# 5409668.net
KiCad netlist of a schematic drawn in EAGLE
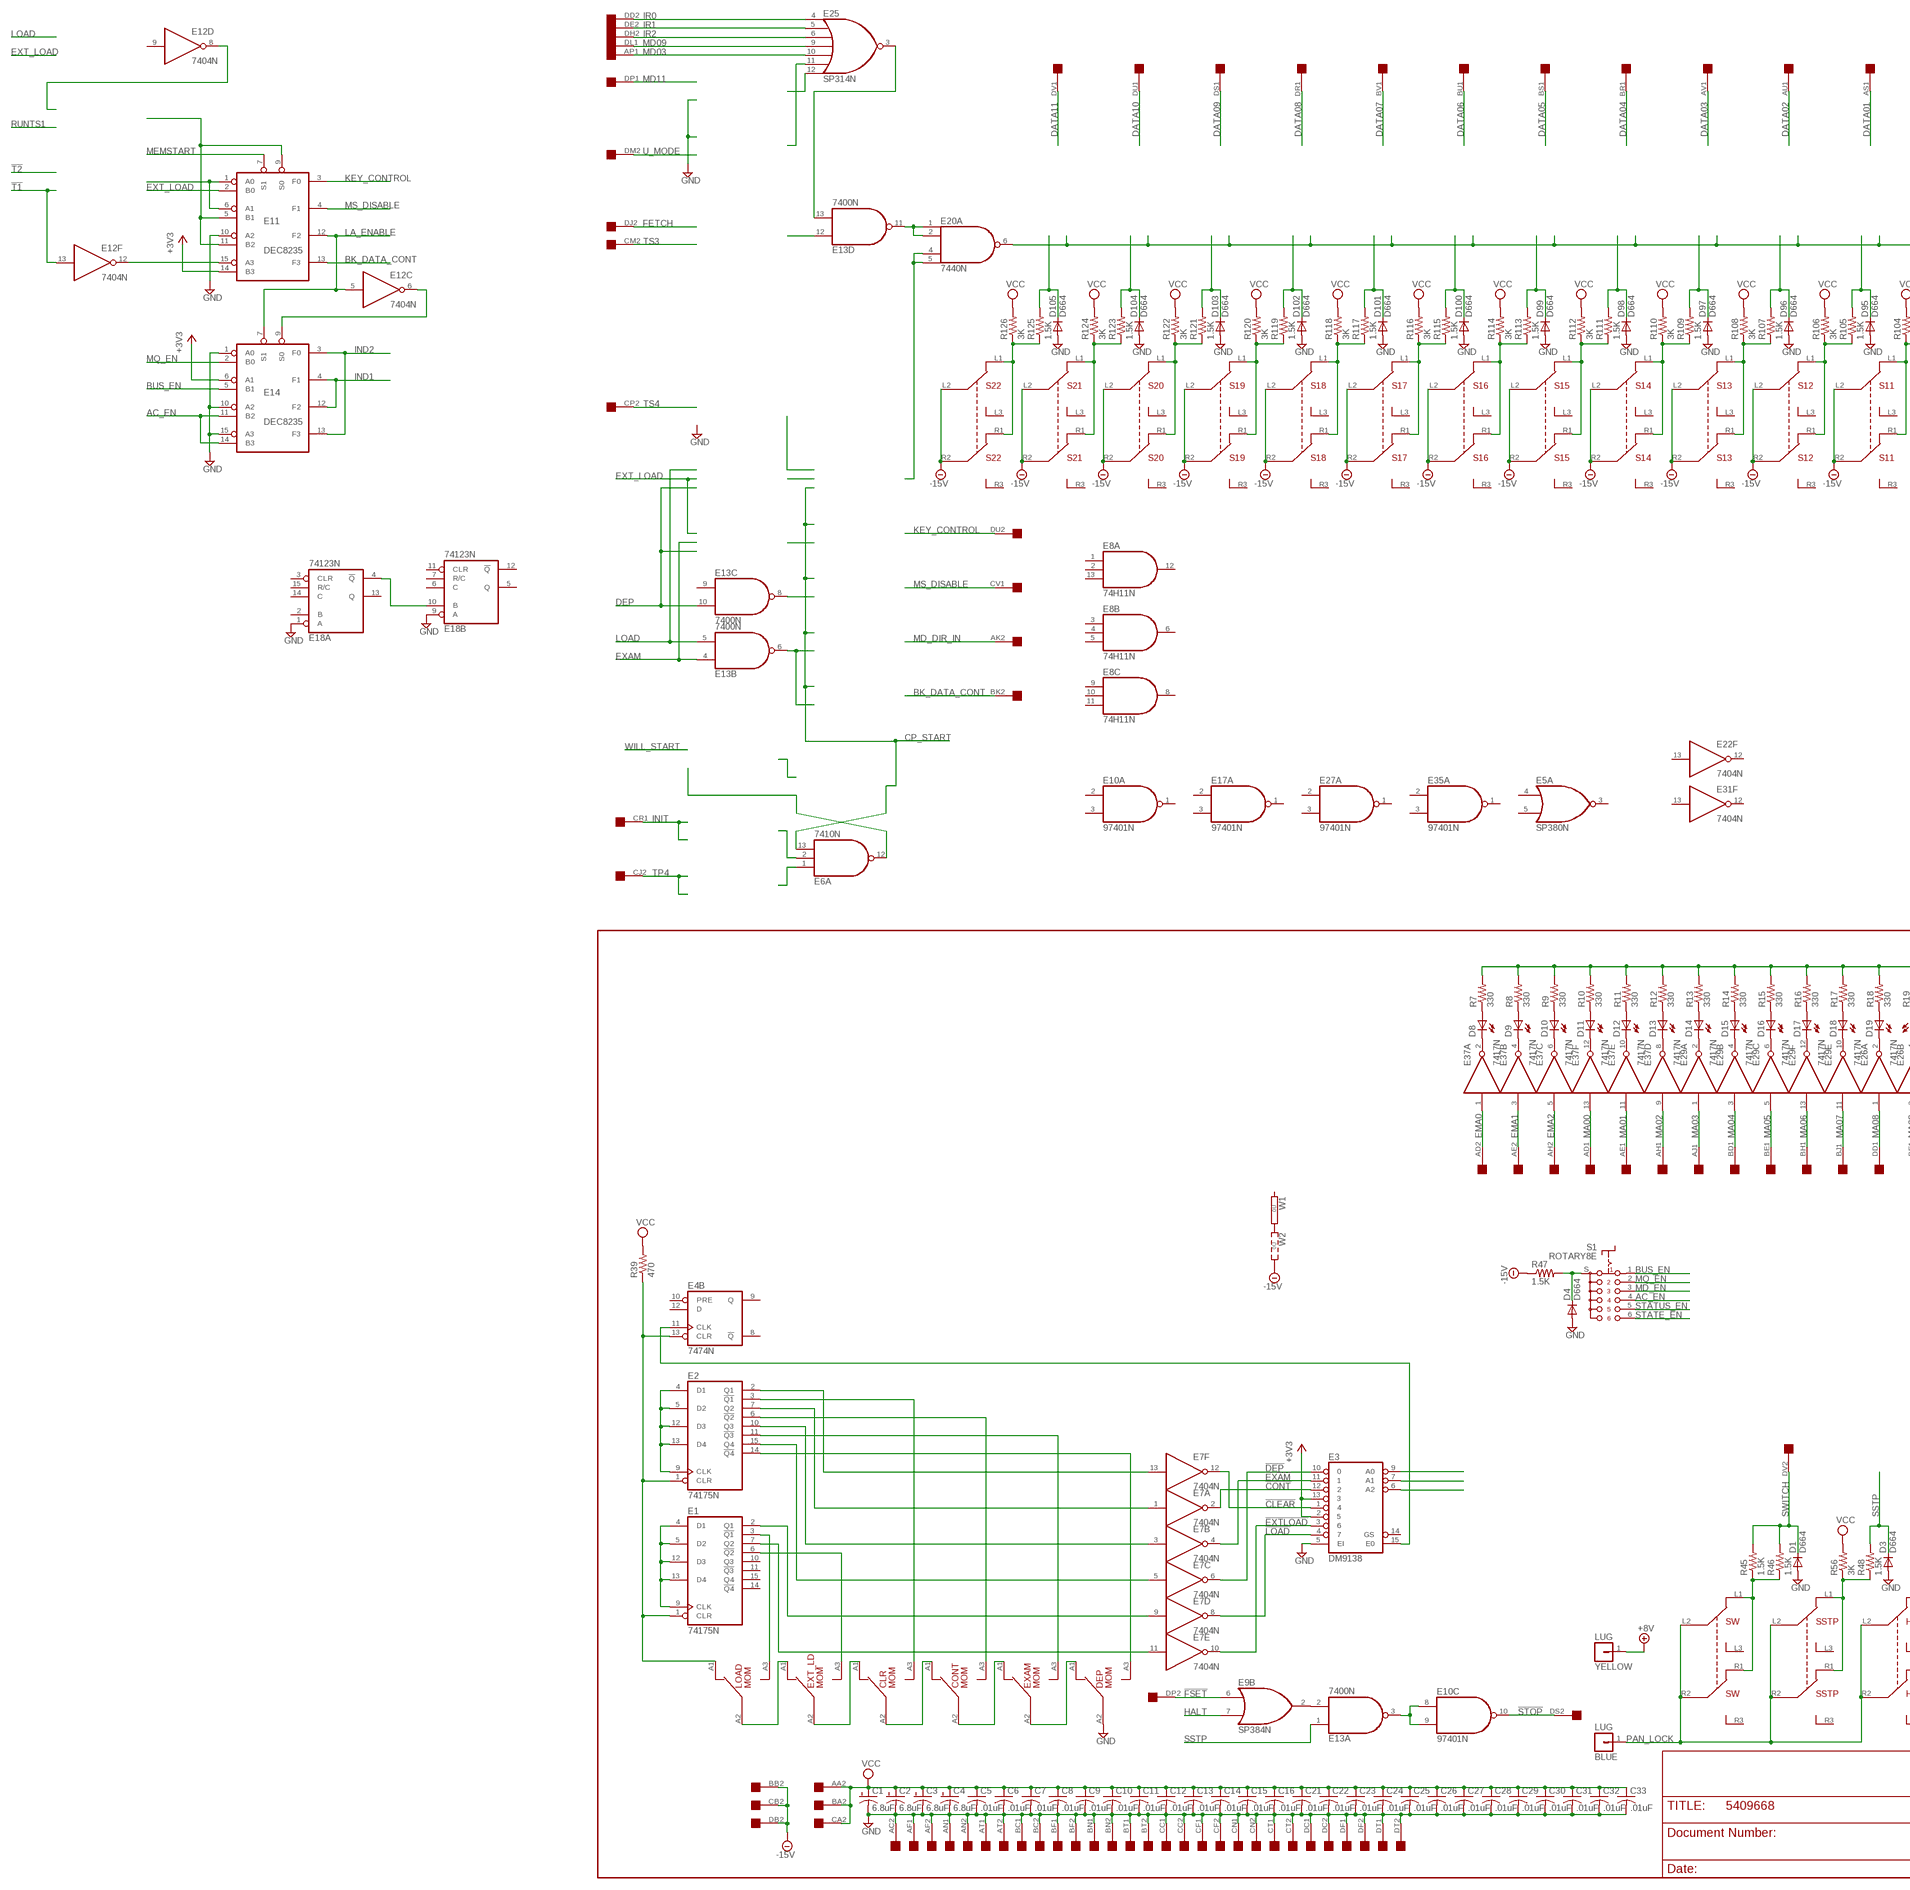
[diagram p0: schematic, sheet 1, part 1 of 2]
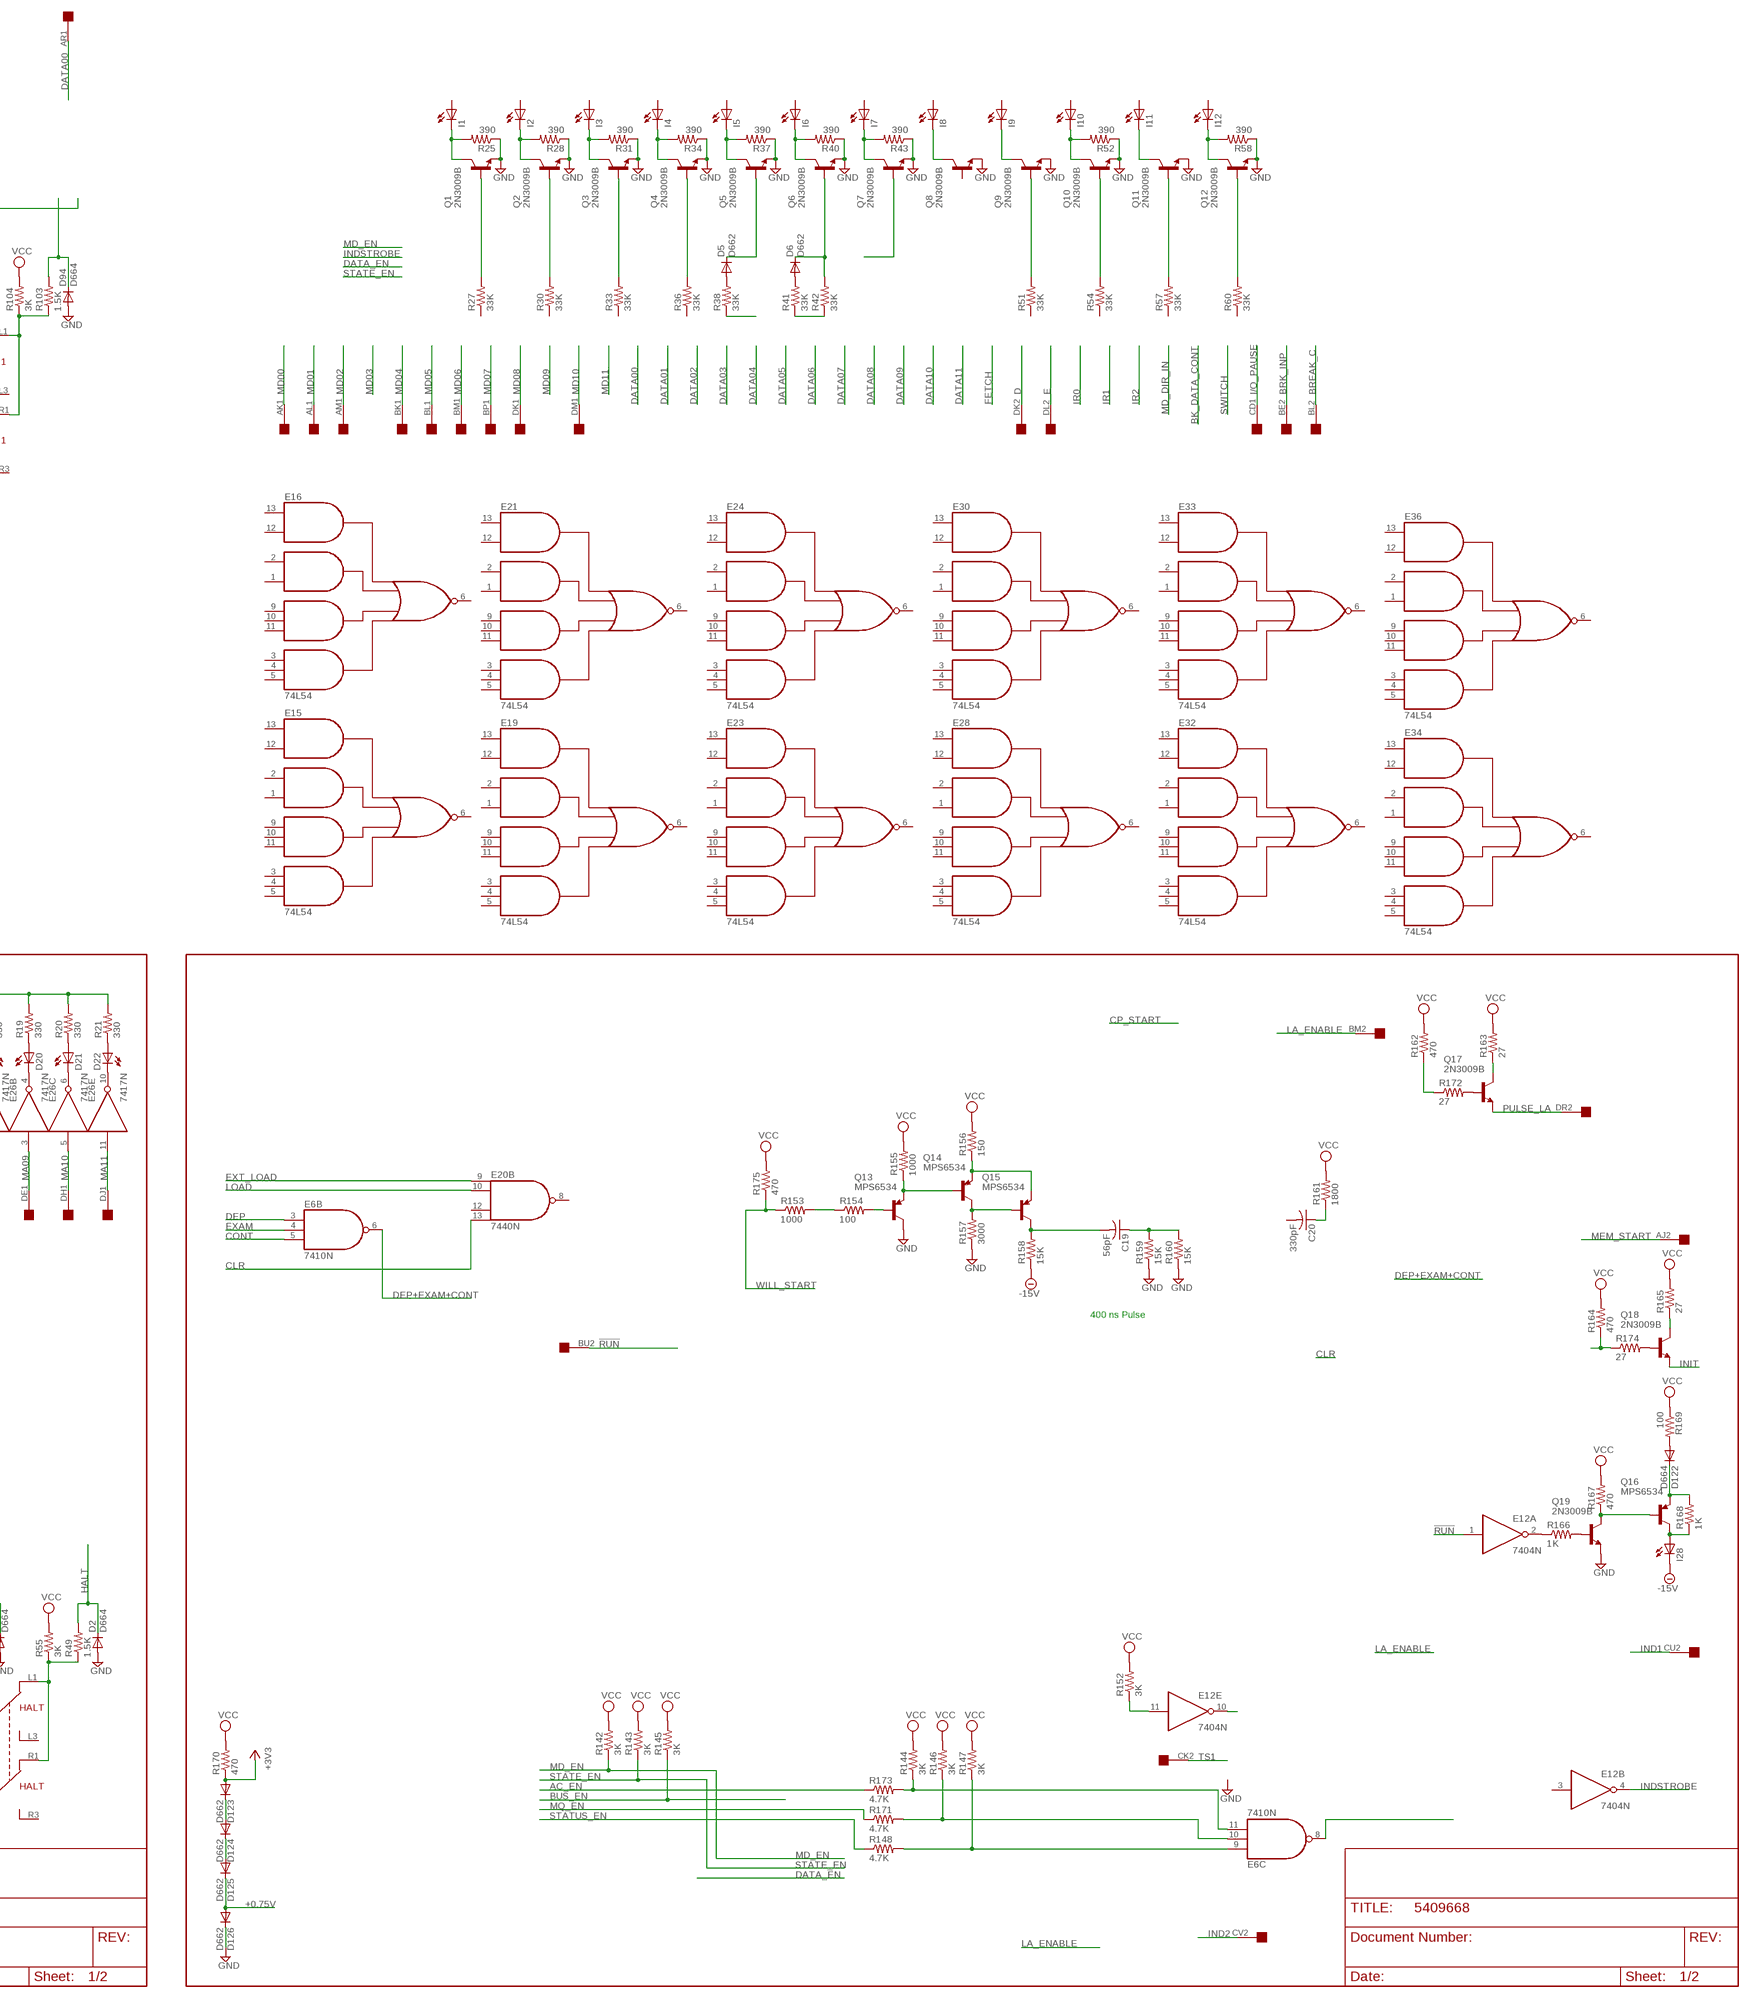
[diagram p1: schematic, sheet 1, part 2 of 2]

(export (version "E")
  (design (tool "Eeschema 10.0.6"))
  (components
    (comp (ref "BLUE")
      (value "LUG")
      (footprint "eagle-import:SPADELUG")
      (libsource (lib "eagle-import") (part "LUG"))
    )
    (comp (ref "C1")
      (value "6.8uF")
      (footprint "eagle-import:E12-8")
      (libsource (lib "eagle-import") (part "CPOL-USE20-8AXIAL"))
    )
    (comp (ref "C2")
      (value "6.8uF")
      (footprint "eagle-import:E12-8")
      (libsource (lib "eagle-import") (part "CPOL-USE20-8AXIAL"))
    )
    (comp (ref "C3")
      (value "6.8uF")
      (footprint "eagle-import:E12-8")
      (libsource (lib "eagle-import") (part "CPOL-USE20-8AXIAL"))
    )
    (comp (ref "C4")
      (value "6.8uF")
      (footprint "eagle-import:E12-8")
      (libsource (lib "eagle-import") (part "CPOL-USE20-8AXIAL"))
    )
    (comp (ref "C5")
      (value ".01uF")
      (footprint "eagle-import:C050-025X075")
      (libsource (lib "eagle-import") (part "C-US050-025X075"))
    )
    (comp (ref "C6")
      (value ".01uF")
      (footprint "eagle-import:C050-025X075")
      (libsource (lib "eagle-import") (part "C-US050-025X075"))
    )
    (comp (ref "C7")
      (value ".01uF")
      (footprint "eagle-import:C050-025X075")
      (libsource (lib "eagle-import") (part "C-US050-025X075"))
    )
    (comp (ref "C8")
      (value ".01uF")
      (footprint "eagle-import:C050-025X075")
      (libsource (lib "eagle-import") (part "C-US050-025X075"))
    )
    (comp (ref "C9")
      (value ".01uF")
      (footprint "eagle-import:C050-025X075")
      (libsource (lib "eagle-import") (part "C-US050-025X075"))
    )
    (comp (ref "C10")
      (value ".01uF")
      (footprint "eagle-import:C050-025X075")
      (libsource (lib "eagle-import") (part "C-US050-025X075"))
    )
    (comp (ref "C11")
      (value ".01uF")
      (footprint "eagle-import:C050-025X075")
      (libsource (lib "eagle-import") (part "C-US050-025X075"))
    )
    (comp (ref "C12")
      (value ".01uF")
      (footprint "eagle-import:C050-025X075")
      (libsource (lib "eagle-import") (part "C-US050-025X075"))
    )
    (comp (ref "C13")
      (value ".01uF")
      (footprint "eagle-import:C050-025X075")
      (libsource (lib "eagle-import") (part "C-US050-025X075"))
    )
    (comp (ref "C14")
      (value ".01uF")
      (footprint "eagle-import:C050-025X075")
      (libsource (lib "eagle-import") (part "C-US050-025X075"))
    )
    (comp (ref "C15")
      (value ".01uF")
      (footprint "eagle-import:C050-025X075")
      (libsource (lib "eagle-import") (part "C-US050-025X075"))
    )
    (comp (ref "C16")
      (value ".01uF")
      (footprint "eagle-import:C050-025X075")
      (libsource (lib "eagle-import") (part "C-US050-025X075"))
    )
    (comp (ref "C19")
      (value "56pF")
      (footprint "eagle-import:C050-025X075")
      (libsource (lib "eagle-import") (part "C-US050-025X075"))
    )
    (comp (ref "C20")
      (value "330pF")
      (footprint "eagle-import:C050-025X075")
      (libsource (lib "eagle-import") (part "C-US050-025X075"))
    )
    (comp (ref "C21")
      (value ".01uF")
      (footprint "eagle-import:C050-025X075")
      (libsource (lib "eagle-import") (part "C-US050-025X075"))
    )
    (comp (ref "C22")
      (value ".01uF")
      (footprint "eagle-import:C050-025X075")
      (libsource (lib "eagle-import") (part "C-US050-025X075"))
    )
    (comp (ref "C23")
      (value ".01uF")
      (footprint "eagle-import:C050-025X075")
      (libsource (lib "eagle-import") (part "C-US050-025X075"))
    )
    (comp (ref "C24")
      (value ".01uF")
      (footprint "eagle-import:C050-025X075")
      (libsource (lib "eagle-import") (part "C-US050-025X075"))
    )
    (comp (ref "C25")
      (value ".01uF")
      (footprint "eagle-import:C050-025X075")
      (libsource (lib "eagle-import") (part "C-US050-025X075"))
    )
    (comp (ref "C26")
      (value ".01uF")
      (footprint "eagle-import:C050-025X075")
      (libsource (lib "eagle-import") (part "C-US050-025X075"))
    )
    (comp (ref "C27")
      (value ".01uF")
      (footprint "eagle-import:C050-025X075")
      (libsource (lib "eagle-import") (part "C-US050-025X075"))
    )
    (comp (ref "C28")
      (value ".01uF")
      (footprint "eagle-import:C050-025X075")
      (libsource (lib "eagle-import") (part "C-US050-025X075"))
    )
    (comp (ref "C29")
      (value ".01uF")
      (footprint "eagle-import:C050-025X075")
      (libsource (lib "eagle-import") (part "C-US050-025X075"))
    )
    (comp (ref "C30")
      (value ".01uF")
      (footprint "eagle-import:C050-025X075")
      (libsource (lib "eagle-import") (part "C-US050-025X075"))
    )
    (comp (ref "C31")
      (value ".01uF")
      (footprint "eagle-import:C050-025X075")
      (libsource (lib "eagle-import") (part "C-US050-025X075"))
    )
    (comp (ref "C32")
      (value ".01uF")
      (footprint "eagle-import:C050-025X075")
      (libsource (lib "eagle-import") (part "C-US050-025X075"))
    )
    (comp (ref "C33")
      (value ".01uF")
      (footprint "eagle-import:C050-025X075")
      (libsource (lib "eagle-import") (part "C-US050-025X075"))
    )
    (comp (ref "CLR")
      (value "SPDT8I")
      (footprint "eagle-import:SPDT8I")
      (libsource (lib "eagle-import") (part "SPDT8I"))
    )
    (comp (ref "CONT")
      (value "SPDT8I")
      (footprint "eagle-import:SPDT8I")
      (libsource (lib "eagle-import") (part "SPDT8I"))
    )
    (comp (ref "D1")
      (value "D664")
      (footprint "eagle-import:DO35-10")
      (libsource (lib "eagle-import") (part "1N4148DO35-10"))
    )
    (comp (ref "D2")
      (value "D664")
      (footprint "eagle-import:DO35-10")
      (libsource (lib "eagle-import") (part "1N4148DO35-10"))
    )
    (comp (ref "D3")
      (value "D664")
      (footprint "eagle-import:DO35-10")
      (libsource (lib "eagle-import") (part "1N4148DO35-10"))
    )
    (comp (ref "D4")
      (value "D664")
      (footprint "eagle-import:DO35-10")
      (libsource (lib "eagle-import") (part "1N4148DO35-10"))
    )
    (comp (ref "D5")
      (value "D662")
      (footprint "eagle-import:DO35-10")
      (libsource (lib "eagle-import") (part "1N4148DO35-10"))
    )
    (comp (ref "D6")
      (value "D662")
      (footprint "eagle-import:DO35-10")
      (libsource (lib "eagle-import") (part "1N4148DO35-10"))
    )
    (comp (ref "D8")
      (value "LED5MM")
      (footprint "eagle-import:LED5MM")
      (libsource (lib "eagle-import") (part "LED5MM"))
    )
    (comp (ref "D9")
      (value "LED5MM")
      (footprint "eagle-import:LED5MM")
      (libsource (lib "eagle-import") (part "LED5MM"))
    )
    (comp (ref "D10")
      (value "LED5MM")
      (footprint "eagle-import:LED5MM")
      (libsource (lib "eagle-import") (part "LED5MM"))
    )
    (comp (ref "D11")
      (value "LED5MM")
      (footprint "eagle-import:LED5MM")
      (libsource (lib "eagle-import") (part "LED5MM"))
    )
    (comp (ref "D12")
      (value "LED5MM")
      (footprint "eagle-import:LED5MM")
      (libsource (lib "eagle-import") (part "LED5MM"))
    )
    (comp (ref "D13")
      (value "LED5MM")
      (footprint "eagle-import:LED5MM")
      (libsource (lib "eagle-import") (part "LED5MM"))
    )
    (comp (ref "D14")
      (value "LED5MM")
      (footprint "eagle-import:LED5MM")
      (libsource (lib "eagle-import") (part "LED5MM"))
    )
    (comp (ref "D15")
      (value "LED5MM")
      (footprint "eagle-import:LED5MM")
      (libsource (lib "eagle-import") (part "LED5MM"))
    )
    (comp (ref "D16")
      (value "LED5MM")
      (footprint "eagle-import:LED5MM")
      (libsource (lib "eagle-import") (part "LED5MM"))
    )
    (comp (ref "D17")
      (value "LED5MM")
      (footprint "eagle-import:LED5MM")
      (libsource (lib "eagle-import") (part "LED5MM"))
    )
    (comp (ref "D18")
      (value "LED5MM")
      (footprint "eagle-import:LED5MM")
      (libsource (lib "eagle-import") (part "LED5MM"))
    )
    (comp (ref "D19")
      (value "LED5MM")
      (footprint "eagle-import:LED5MM")
      (libsource (lib "eagle-import") (part "LED5MM"))
    )
    (comp (ref "D20")
      (value "LED5MM")
      (footprint "eagle-import:LED5MM")
      (libsource (lib "eagle-import") (part "LED5MM"))
    )
    (comp (ref "D21")
      (value "LED5MM")
      (footprint "eagle-import:LED5MM")
      (libsource (lib "eagle-import") (part "LED5MM"))
    )
    (comp (ref "D22")
      (value "LED5MM")
      (footprint "eagle-import:LED5MM")
      (libsource (lib "eagle-import") (part "LED5MM"))
    )
    (comp (ref "D94")
      (value "D664")
      (footprint "eagle-import:DO35-10")
      (libsource (lib "eagle-import") (part "1N4148DO35-10"))
    )
    (comp (ref "D95")
      (value "D664")
      (footprint "eagle-import:DO35-10")
      (libsource (lib "eagle-import") (part "1N4148DO35-10"))
    )
    (comp (ref "D96")
      (value "D664")
      (footprint "eagle-import:DO35-10")
      (libsource (lib "eagle-import") (part "1N4148DO35-10"))
    )
    (comp (ref "D97")
      (value "D664")
      (footprint "eagle-import:DO35-10")
      (libsource (lib "eagle-import") (part "1N4148DO35-10"))
    )
    (comp (ref "D98")
      (value "D664")
      (footprint "eagle-import:DO35-10")
      (libsource (lib "eagle-import") (part "1N4148DO35-10"))
    )
    (comp (ref "D99")
      (value "D664")
      (footprint "eagle-import:DO35-10")
      (libsource (lib "eagle-import") (part "1N4148DO35-10"))
    )
    (comp (ref "D100")
      (value "D664")
      (footprint "eagle-import:DO35-10")
      (libsource (lib "eagle-import") (part "1N4148DO35-10"))
    )
    (comp (ref "D101")
      (value "D664")
      (footprint "eagle-import:DO35-10")
      (libsource (lib "eagle-import") (part "1N4148DO35-10"))
    )
    (comp (ref "D102")
      (value "D664")
      (footprint "eagle-import:DO35-10")
      (libsource (lib "eagle-import") (part "1N4148DO35-10"))
    )
    (comp (ref "D103")
      (value "D664")
      (footprint "eagle-import:DO35-10")
      (libsource (lib "eagle-import") (part "1N4148DO35-10"))
    )
    (comp (ref "D104")
      (value "D664")
      (footprint "eagle-import:DO35-10")
      (libsource (lib "eagle-import") (part "1N4148DO35-10"))
    )
    (comp (ref "D105")
      (value "D664")
      (footprint "eagle-import:DO35-10")
      (libsource (lib "eagle-import") (part "1N4148DO35-10"))
    )
    (comp (ref "D122")
      (value "D664")
      (footprint "eagle-import:DO35-10")
      (libsource (lib "eagle-import") (part "1N4148DO35-10"))
    )
    (comp (ref "D123")
      (value "D662")
      (footprint "eagle-import:DO35-10")
      (libsource (lib "eagle-import") (part "1N4148DO35-10"))
    )
    (comp (ref "D124")
      (value "D662")
      (footprint "eagle-import:DO35-10")
      (libsource (lib "eagle-import") (part "1N4148DO35-10"))
    )
    (comp (ref "D125")
      (value "D662")
      (footprint "eagle-import:DO35-10")
      (libsource (lib "eagle-import") (part "1N4148DO35-10"))
    )
    (comp (ref "D126")
      (value "D662")
      (footprint "eagle-import:DO35-10")
      (libsource (lib "eagle-import") (part "1N4148DO35-10"))
    )
    (comp (ref "DEP")
      (value "SPDT8I")
      (footprint "eagle-import:SPDT8I")
      (libsource (lib "eagle-import") (part "SPDT8I"))
    )
    (comp (ref "E1")
      (value "74175N")
      (footprint "eagle-import:DIL16")
      (libsource (lib "eagle-import") (part "74175N"))
    )
    (comp (ref "E2")
      (value "74175N")
      (footprint "eagle-import:DIL16")
      (libsource (lib "eagle-import") (part "74175N"))
    )
    (comp (ref "E3")
      (value "DM9138")
      (footprint "eagle-import:DIL16")
      (libsource (lib "eagle-import") (part "74348NLS"))
    )
    (comp (ref "E4")
      (value "7474N")
      (footprint "eagle-import:DIL14")
      (libsource (lib "eagle-import") (part "7474NS"))
    )
    (comp (ref "E5")
      (value "SP380N")
      (footprint "eagle-import:DIL14")
      (libsource (lib "eagle-import") (part "SP380N"))
    )
    (comp (ref "E6")
      (value "7410N")
      (footprint "eagle-import:DIL14")
      (libsource (lib "eagle-import") (part "7410N"))
    )
    (comp (ref "E7")
      (value "7404N")
      (footprint "eagle-import:DIL14")
      (libsource (lib "eagle-import") (part "7404N"))
    )
    (comp (ref "E8")
      (value "74H11N")
      (footprint "eagle-import:DIL14")
      (libsource (lib "eagle-import") (part "7411NS"))
    )
    (comp (ref "E9")
      (value "SP384N")
      (footprint "eagle-import:DIL14")
      (libsource (lib "eagle-import") (part "SP384N"))
    )
    (comp (ref "E10")
      (value "97401N")
      (footprint "eagle-import:DIL14")
      (libsource (lib "eagle-import") (part "7401NLS"))
    )
    (comp (ref "E11")
      (value "DEC8235")
      (footprint "eagle-import:DIL16")
      (libsource (lib "eagle-import") (part "DEC8235"))
    )
    (comp (ref "E12")
      (value "7404N")
      (footprint "eagle-import:DIL14")
      (libsource (lib "eagle-import") (part "7404N"))
    )
    (comp (ref "E13")
      (value "7400N")
      (footprint "eagle-import:DIL14")
      (libsource (lib "eagle-import") (part "7400N"))
    )
    (comp (ref "E14")
      (value "DEC8235")
      (footprint "eagle-import:DIL16")
      (libsource (lib "eagle-import") (part "DEC8235"))
    )
    (comp (ref "E15")
      (value "74L54")
      (footprint "eagle-import:DIL14")
      (libsource (lib "eagle-import") (part "74LS54"))
    )
    (comp (ref "E16")
      (value "74L54")
      (footprint "eagle-import:DIL14")
      (libsource (lib "eagle-import") (part "74LS54"))
    )
    (comp (ref "E17")
      (value "97401N")
      (footprint "eagle-import:DIL14")
      (libsource (lib "eagle-import") (part "7401NLS"))
    )
    (comp (ref "E18")
      (value "74123N")
      (footprint "eagle-import:DIL16")
      (libsource (lib "eagle-import") (part "74123N"))
    )
    (comp (ref "E19")
      (value "74L54")
      (footprint "eagle-import:DIL14")
      (libsource (lib "eagle-import") (part "74LS54"))
    )
    (comp (ref "E20")
      (value "7440N")
      (footprint "eagle-import:DIL14")
      (libsource (lib "eagle-import") (part "7420NS"))
    )
    (comp (ref "E21")
      (value "74L54")
      (footprint "eagle-import:DIL14")
      (libsource (lib "eagle-import") (part "74LS54"))
    )
    (comp (ref "E22")
      (value "7404N")
      (footprint "eagle-import:DIL14")
      (libsource (lib "eagle-import") (part "7404N"))
    )
    (comp (ref "E23")
      (value "74L54")
      (footprint "eagle-import:DIL14")
      (libsource (lib "eagle-import") (part "74LS54"))
    )
    (comp (ref "E24")
      (value "74L54")
      (footprint "eagle-import:DIL14")
      (libsource (lib "eagle-import") (part "74LS54"))
    )
    (comp (ref "E25")
      (value "SP314N")
      (footprint "eagle-import:DIL14")
      (libsource (lib "eagle-import") (part "SP314N"))
    )
    (comp (ref "E26")
      (value "7417N")
      (footprint "eagle-import:DIL14")
      (libsource (lib "eagle-import") (part "7417N"))
    )
    (comp (ref "E27")
      (value "97401N")
      (footprint "eagle-import:DIL14")
      (libsource (lib "eagle-import") (part "7401NLS"))
    )
    (comp (ref "E28")
      (value "74L54")
      (footprint "eagle-import:DIL14")
      (libsource (lib "eagle-import") (part "74LS54"))
    )
    (comp (ref "E29")
      (value "7417N")
      (footprint "eagle-import:DIL14")
      (libsource (lib "eagle-import") (part "7417N"))
    )
    (comp (ref "E30")
      (value "74L54")
      (footprint "eagle-import:DIL14")
      (libsource (lib "eagle-import") (part "74LS54"))
    )
    (comp (ref "E31")
      (value "7404N")
      (footprint "eagle-import:DIL14")
      (libsource (lib "eagle-import") (part "7404N"))
    )
    (comp (ref "E32")
      (value "74L54")
      (footprint "eagle-import:DIL14")
      (libsource (lib "eagle-import") (part "74LS54"))
    )
    (comp (ref "E33")
      (value "74L54")
      (footprint "eagle-import:DIL14")
      (libsource (lib "eagle-import") (part "74LS54"))
    )
    (comp (ref "E34")
      (value "74L54")
      (footprint "eagle-import:DIL14")
      (libsource (lib "eagle-import") (part "74LS54"))
    )
    (comp (ref "E35")
      (value "97401N")
      (footprint "eagle-import:DIL14")
      (libsource (lib "eagle-import") (part "7401NLS"))
    )
    (comp (ref "E36")
      (value "74L54")
      (footprint "eagle-import:DIL14")
      (libsource (lib "eagle-import") (part "74LS54"))
    )
    (comp (ref "E37")
      (value "7417N")
      (footprint "eagle-import:DIL14")
      (libsource (lib "eagle-import") (part "7417N"))
    )
    (comp (ref "EXAM")
      (value "SPDT8I")
      (footprint "eagle-import:SPDT8I")
      (libsource (lib "eagle-import") (part "SPDT8I"))
    )
    (comp (ref "EXT_LD")
      (value "SPDT8I")
      (footprint "eagle-import:SPDT8I")
      (libsource (lib "eagle-import") (part "SPDT8I"))
    )
    (comp (ref "HALT")
      (value "DPDT8I")
      (footprint "eagle-import:DPDT8I")
      (libsource (lib "eagle-import") (part "DPDT8I"))
    )
    (comp (ref "I1")
      (value "LED5MM")
      (footprint "eagle-import:LED5MM")
      (libsource (lib "eagle-import") (part "LED5MM"))
    )
    (comp (ref "I2")
      (value "LED5MM")
      (footprint "eagle-import:LED5MM")
      (libsource (lib "eagle-import") (part "LED5MM"))
    )
    (comp (ref "I3")
      (value "LED5MM")
      (footprint "eagle-import:LED5MM")
      (libsource (lib "eagle-import") (part "LED5MM"))
    )
    (comp (ref "I4")
      (value "LED5MM")
      (footprint "eagle-import:LED5MM")
      (libsource (lib "eagle-import") (part "LED5MM"))
    )
    (comp (ref "I5")
      (value "LED5MM")
      (footprint "eagle-import:LED5MM")
      (libsource (lib "eagle-import") (part "LED5MM"))
    )
    (comp (ref "I6")
      (value "LED5MM")
      (footprint "eagle-import:LED5MM")
      (libsource (lib "eagle-import") (part "LED5MM"))
    )
    (comp (ref "I7")
      (value "LED5MM")
      (footprint "eagle-import:LED5MM")
      (libsource (lib "eagle-import") (part "LED5MM"))
    )
    (comp (ref "I8")
      (value "LED5MM")
      (footprint "eagle-import:LED5MM")
      (libsource (lib "eagle-import") (part "LED5MM"))
    )
    (comp (ref "I9")
      (value "LED5MM")
      (footprint "eagle-import:LED5MM")
      (libsource (lib "eagle-import") (part "LED5MM"))
    )
    (comp (ref "I10")
      (value "LED5MM")
      (footprint "eagle-import:LED5MM")
      (libsource (lib "eagle-import") (part "LED5MM"))
    )
    (comp (ref "I11")
      (value "LED5MM")
      (footprint "eagle-import:LED5MM")
      (libsource (lib "eagle-import") (part "LED5MM"))
    )
    (comp (ref "I12")
      (value "LED5MM")
      (footprint "eagle-import:LED5MM")
      (libsource (lib "eagle-import") (part "LED5MM"))
    )
    (comp (ref "I28")
      (value "LED5MM")
      (footprint "eagle-import:LED5MM")
      (libsource (lib "eagle-import") (part "LED5MM"))
    )
    (comp (ref "LOAD")
      (value "SPDT8I")
      (footprint "eagle-import:SPDT8I")
      (libsource (lib "eagle-import") (part "SPDT8I"))
    )
    (comp (ref "Q1")
      (value "2N3009B")
      (footprint "eagle-import:TO39")
      (libsource (lib "eagle-import") (part "2N3019"))
    )
    (comp (ref "Q2")
      (value "2N3009B")
      (footprint "eagle-import:TO39")
      (libsource (lib "eagle-import") (part "2N3019"))
    )
    (comp (ref "Q3")
      (value "2N3009B")
      (footprint "eagle-import:TO39")
      (libsource (lib "eagle-import") (part "2N3019"))
    )
    (comp (ref "Q4")
      (value "2N3009B")
      (footprint "eagle-import:TO39")
      (libsource (lib "eagle-import") (part "2N3019"))
    )
    (comp (ref "Q5")
      (value "2N3009B")
      (footprint "eagle-import:TO39")
      (libsource (lib "eagle-import") (part "2N3019"))
    )
    (comp (ref "Q6")
      (value "2N3009B")
      (footprint "eagle-import:TO39")
      (libsource (lib "eagle-import") (part "2N3019"))
    )
    (comp (ref "Q7")
      (value "2N3009B")
      (footprint "eagle-import:TO39")
      (libsource (lib "eagle-import") (part "2N3019"))
    )
    (comp (ref "Q8")
      (value "2N3009B")
      (footprint "eagle-import:TO39")
      (libsource (lib "eagle-import") (part "2N3019"))
    )
    (comp (ref "Q9")
      (value "2N3009B")
      (footprint "eagle-import:TO39")
      (libsource (lib "eagle-import") (part "2N3019"))
    )
    (comp (ref "Q10")
      (value "2N3009B")
      (footprint "eagle-import:TO39")
      (libsource (lib "eagle-import") (part "2N3019"))
    )
    (comp (ref "Q11")
      (value "2N3009B")
      (footprint "eagle-import:TO39")
      (libsource (lib "eagle-import") (part "2N3019"))
    )
    (comp (ref "Q12")
      (value "2N3009B")
      (footprint "eagle-import:TO39")
      (libsource (lib "eagle-import") (part "2N3019"))
    )
    (comp (ref "Q13")
      (value "MPS6534")
      (footprint "eagle-import:TO39")
      (libsource (lib "eagle-import") (part "2N3637"))
    )
    (comp (ref "Q14")
      (value "MPS6534")
      (footprint "eagle-import:TO39")
      (libsource (lib "eagle-import") (part "2N3637"))
    )
    (comp (ref "Q15")
      (value "MPS6534")
      (footprint "eagle-import:TO39")
      (libsource (lib "eagle-import") (part "2N3637"))
    )
    (comp (ref "Q16")
      (value "MPS6534")
      (footprint "eagle-import:TO39")
      (libsource (lib "eagle-import") (part "2N3637"))
    )
    (comp (ref "Q17")
      (value "2N3009B")
      (footprint "eagle-import:TO39")
      (libsource (lib "eagle-import") (part "2N3019"))
    )
    (comp (ref "Q18")
      (value "2N3009B")
      (footprint "eagle-import:TO39")
      (libsource (lib "eagle-import") (part "2N3019"))
    )
    (comp (ref "Q19")
      (value "2N3009B")
      (footprint "eagle-import:TO39")
      (libsource (lib "eagle-import") (part "2N3019"))
    )
    (comp (ref "R7")
      (value "330")
      (footprint "eagle-import:0207_10")
      (libsource (lib "eagle-import") (part "R-US_0207/10"))
    )
    (comp (ref "R8")
      (value "330")
      (footprint "eagle-import:0207_10")
      (libsource (lib "eagle-import") (part "R-US_0207/10"))
    )
    (comp (ref "R9")
      (value "330")
      (footprint "eagle-import:0207_10")
      (libsource (lib "eagle-import") (part "R-US_0207/10"))
    )
    (comp (ref "R10")
      (value "330")
      (footprint "eagle-import:0207_10")
      (libsource (lib "eagle-import") (part "R-US_0207/10"))
    )
    (comp (ref "R11")
      (value "330")
      (footprint "eagle-import:0207_10")
      (libsource (lib "eagle-import") (part "R-US_0207/10"))
    )
    (comp (ref "R12")
      (value "330")
      (footprint "eagle-import:0207_10")
      (libsource (lib "eagle-import") (part "R-US_0207/10"))
    )
    (comp (ref "R13")
      (value "330")
      (footprint "eagle-import:0207_10")
      (libsource (lib "eagle-import") (part "R-US_0207/10"))
    )
    (comp (ref "R14")
      (value "330")
      (footprint "eagle-import:0207_10")
      (libsource (lib "eagle-import") (part "R-US_0207/10"))
    )
    (comp (ref "R15")
      (value "330")
      (footprint "eagle-import:0207_10")
      (libsource (lib "eagle-import") (part "R-US_0207/10"))
    )
    (comp (ref "R16")
      (value "330")
      (footprint "eagle-import:0207_10")
      (libsource (lib "eagle-import") (part "R-US_0207/10"))
    )
    (comp (ref "R17")
      (value "330")
      (footprint "eagle-import:0207_10")
      (libsource (lib "eagle-import") (part "R-US_0207/10"))
    )
    (comp (ref "R18")
      (value "330")
      (footprint "eagle-import:0207_10")
      (libsource (lib "eagle-import") (part "R-US_0207/10"))
    )
    (comp (ref "R19")
      (value "330")
      (footprint "eagle-import:0207_10")
      (libsource (lib "eagle-import") (part "R-US_0207/10"))
    )
    (comp (ref "R20")
      (value "330")
      (footprint "eagle-import:0207_10")
      (libsource (lib "eagle-import") (part "R-US_0207/10"))
    )
    (comp (ref "R21")
      (value "330")
      (footprint "eagle-import:0207_10")
      (libsource (lib "eagle-import") (part "R-US_0207/10"))
    )
    (comp (ref "R25")
      (value "390")
      (footprint "eagle-import:0207_10")
      (libsource (lib "eagle-import") (part "R-US_0207/10"))
    )
    (comp (ref "R27")
      (value "33K")
      (footprint "eagle-import:0207_10")
      (libsource (lib "eagle-import") (part "R-US_0207/10"))
    )
    (comp (ref "R28")
      (value "390")
      (footprint "eagle-import:0207_10")
      (libsource (lib "eagle-import") (part "R-US_0207/10"))
    )
    (comp (ref "R30")
      (value "33K")
      (footprint "eagle-import:0207_10")
      (libsource (lib "eagle-import") (part "R-US_0207/10"))
    )
    (comp (ref "R31")
      (value "390")
      (footprint "eagle-import:0207_10")
      (libsource (lib "eagle-import") (part "R-US_0207/10"))
    )
    (comp (ref "R33")
      (value "33K")
      (footprint "eagle-import:0207_10")
      (libsource (lib "eagle-import") (part "R-US_0207/10"))
    )
    (comp (ref "R34")
      (value "390")
      (footprint "eagle-import:0207_10")
      (libsource (lib "eagle-import") (part "R-US_0207/10"))
    )
    (comp (ref "R36")
      (value "33K")
      (footprint "eagle-import:0207_10")
      (libsource (lib "eagle-import") (part "R-US_0207/10"))
    )
    (comp (ref "R37")
      (value "390")
      (footprint "eagle-import:0207_10")
      (libsource (lib "eagle-import") (part "R-US_0207/10"))
    )
    (comp (ref "R38")
      (value "33K")
      (footprint "eagle-import:0207_10")
      (libsource (lib "eagle-import") (part "R-US_0207/10"))
    )
    (comp (ref "R39")
      (value "470")
      (footprint "eagle-import:0207_10")
      (libsource (lib "eagle-import") (part "R-US_0207/10"))
    )
    (comp (ref "R40")
      (value "390")
      (footprint "eagle-import:0207_10")
      (libsource (lib "eagle-import") (part "R-US_0207/10"))
    )
    (comp (ref "R41")
      (value "33K")
      (footprint "eagle-import:0207_10")
      (libsource (lib "eagle-import") (part "R-US_0207/10"))
    )
    (comp (ref "R42")
      (value "33K")
      (footprint "eagle-import:0207_10")
      (libsource (lib "eagle-import") (part "R-US_0207/10"))
    )
    (comp (ref "R43")
      (value "390")
      (footprint "eagle-import:0207_10")
      (libsource (lib "eagle-import") (part "R-US_0207/10"))
    )
    (comp (ref "R45")
      (value "1.5K")
      (footprint "eagle-import:0207_10")
      (libsource (lib "eagle-import") (part "R-US_0207/10"))
    )
    (comp (ref "R46")
      (value "1.5K")
      (footprint "eagle-import:0207_10")
      (libsource (lib "eagle-import") (part "R-US_0207/10"))
    )
    (comp (ref "R47")
      (value "1.5K")
      (footprint "eagle-import:0207_10")
      (libsource (lib "eagle-import") (part "R-US_0207/10"))
    )
    (comp (ref "R48")
      (value "1.5K")
      (footprint "eagle-import:0207_10")
      (libsource (lib "eagle-import") (part "R-US_0207/10"))
    )
    (comp (ref "R49")
      (value "1.5K")
      (footprint "eagle-import:0207_10")
      (libsource (lib "eagle-import") (part "R-US_0207/10"))
    )
    (comp (ref "R51")
      (value "33K")
      (footprint "eagle-import:0207_10")
      (libsource (lib "eagle-import") (part "R-US_0207/10"))
    )
    (comp (ref "R52")
      (value "390")
      (footprint "eagle-import:0207_10")
      (libsource (lib "eagle-import") (part "R-US_0207/10"))
    )
    (comp (ref "R54")
      (value "33K")
      (footprint "eagle-import:0207_10")
      (libsource (lib "eagle-import") (part "R-US_0207/10"))
    )
    (comp (ref "R55")
      (value "3K")
      (footprint "eagle-import:0207_10")
      (libsource (lib "eagle-import") (part "R-US_0207/10"))
    )
    (comp (ref "R56")
      (value "3K")
      (footprint "eagle-import:0207_10")
      (libsource (lib "eagle-import") (part "R-US_0207/10"))
    )
    (comp (ref "R57")
      (value "33K")
      (footprint "eagle-import:0207_10")
      (libsource (lib "eagle-import") (part "R-US_0207/10"))
    )
    (comp (ref "R58")
      (value "390")
      (footprint "eagle-import:0207_10")
      (libsource (lib "eagle-import") (part "R-US_0207/10"))
    )
    (comp (ref "R60")
      (value "33K")
      (footprint "eagle-import:0207_10")
      (libsource (lib "eagle-import") (part "R-US_0207/10"))
    )
    (comp (ref "R103")
      (value "1.5K")
      (footprint "eagle-import:0207_10")
      (libsource (lib "eagle-import") (part "R-US_0207/10"))
    )
    (comp (ref "R104")
      (value "3K")
      (footprint "eagle-import:0207_10")
      (libsource (lib "eagle-import") (part "R-US_0207/10"))
    )
    (comp (ref "R105")
      (value "1.5K")
      (footprint "eagle-import:0207_10")
      (libsource (lib "eagle-import") (part "R-US_0207/10"))
    )
    (comp (ref "R106")
      (value "3K")
      (footprint "eagle-import:0207_10")
      (libsource (lib "eagle-import") (part "R-US_0207/10"))
    )
    (comp (ref "R107")
      (value "1.5K")
      (footprint "eagle-import:0207_10")
      (libsource (lib "eagle-import") (part "R-US_0207/10"))
    )
    (comp (ref "R108")
      (value "3K")
      (footprint "eagle-import:0207_10")
      (libsource (lib "eagle-import") (part "R-US_0207/10"))
    )
    (comp (ref "R109")
      (value "1.5K")
      (footprint "eagle-import:0207_10")
      (libsource (lib "eagle-import") (part "R-US_0207/10"))
    )
    (comp (ref "R110")
      (value "3K")
      (footprint "eagle-import:0207_10")
      (libsource (lib "eagle-import") (part "R-US_0207/10"))
    )
    (comp (ref "R111")
      (value "1.5K")
      (footprint "eagle-import:0207_10")
      (libsource (lib "eagle-import") (part "R-US_0207/10"))
    )
    (comp (ref "R112")
      (value "3K")
      (footprint "eagle-import:0207_10")
      (libsource (lib "eagle-import") (part "R-US_0207/10"))
    )
    (comp (ref "R113")
      (value "1.5K")
      (footprint "eagle-import:0207_10")
      (libsource (lib "eagle-import") (part "R-US_0207/10"))
    )
    (comp (ref "R114")
      (value "3K")
      (footprint "eagle-import:0207_10")
      (libsource (lib "eagle-import") (part "R-US_0207/10"))
    )
    (comp (ref "R115")
      (value "1.5K")
      (footprint "eagle-import:0207_10")
      (libsource (lib "eagle-import") (part "R-US_0207/10"))
    )
    (comp (ref "R116")
      (value "3K")
      (footprint "eagle-import:0207_10")
      (libsource (lib "eagle-import") (part "R-US_0207/10"))
    )
    (comp (ref "R117")
      (value "1.5K")
      (footprint "eagle-import:0207_10")
      (libsource (lib "eagle-import") (part "R-US_0207/10"))
    )
    (comp (ref "R118")
      (value "3K")
      (footprint "eagle-import:0207_10")
      (libsource (lib "eagle-import") (part "R-US_0207/10"))
    )
    (comp (ref "R119")
      (value "1.5K")
      (footprint "eagle-import:0207_10")
      (libsource (lib "eagle-import") (part "R-US_0207/10"))
    )
    (comp (ref "R120")
      (value "3K")
      (footprint "eagle-import:0207_10")
      (libsource (lib "eagle-import") (part "R-US_0207/10"))
    )
    (comp (ref "R121")
      (value "1.5K")
      (footprint "eagle-import:0207_10")
      (libsource (lib "eagle-import") (part "R-US_0207/10"))
    )
    (comp (ref "R122")
      (value "3K")
      (footprint "eagle-import:0207_10")
      (libsource (lib "eagle-import") (part "R-US_0207/10"))
    )
    (comp (ref "R123")
      (value "1.5K")
      (footprint "eagle-import:0207_10")
      (libsource (lib "eagle-import") (part "R-US_0207/10"))
    )
    (comp (ref "R124")
      (value "3K")
      (footprint "eagle-import:0207_10")
      (libsource (lib "eagle-import") (part "R-US_0207/10"))
    )
    (comp (ref "R125")
      (value "1.5K")
      (footprint "eagle-import:0207_10")
      (libsource (lib "eagle-import") (part "R-US_0207/10"))
    )
    (comp (ref "R126")
      (value "3K")
      (footprint "eagle-import:0207_10")
      (libsource (lib "eagle-import") (part "R-US_0207/10"))
    )
    (comp (ref "R142")
      (value "3K")
      (footprint "eagle-import:0207_10")
      (libsource (lib "eagle-import") (part "R-US_0207/10"))
    )
    (comp (ref "R143")
      (value "3K")
      (footprint "eagle-import:0207_10")
      (libsource (lib "eagle-import") (part "R-US_0207/10"))
    )
    (comp (ref "R144")
      (value "3K")
      (footprint "eagle-import:0207_10")
      (libsource (lib "eagle-import") (part "R-US_0207/10"))
    )
    (comp (ref "R145")
      (value "3K")
      (footprint "eagle-import:0207_10")
      (libsource (lib "eagle-import") (part "R-US_0207/10"))
    )
    (comp (ref "R146")
      (value "3K")
      (footprint "eagle-import:0207_10")
      (libsource (lib "eagle-import") (part "R-US_0207/10"))
    )
    (comp (ref "R147")
      (value "3K")
      (footprint "eagle-import:0207_10")
      (libsource (lib "eagle-import") (part "R-US_0207/10"))
    )
    (comp (ref "R148")
      (value "4.7K")
      (footprint "eagle-import:0207_10")
      (libsource (lib "eagle-import") (part "R-US_0207/10"))
    )
    (comp (ref "R152")
      (value "3K")
      (footprint "eagle-import:0207_10")
      (libsource (lib "eagle-import") (part "R-US_0207/10"))
    )
    (comp (ref "R153")
      (value "1000")
      (footprint "eagle-import:0207_10")
      (libsource (lib "eagle-import") (part "R-US_0207/10"))
    )
    (comp (ref "R154")
      (value "100")
      (footprint "eagle-import:0207_10")
      (libsource (lib "eagle-import") (part "R-US_0207/10"))
    )
    (comp (ref "R155")
      (value "1000")
      (footprint "eagle-import:0207_10")
      (libsource (lib "eagle-import") (part "R-US_0207/10"))
    )
    (comp (ref "R156")
      (value "150")
      (footprint "eagle-import:0207_10")
      (libsource (lib "eagle-import") (part "R-US_0207/10"))
    )
    (comp (ref "R157")
      (value "3000")
      (footprint "eagle-import:0207_10")
      (libsource (lib "eagle-import") (part "R-US_0207/10"))
    )
    (comp (ref "R158")
      (value "15K")
      (footprint "eagle-import:0207_10")
      (libsource (lib "eagle-import") (part "R-US_0207/10"))
    )
    (comp (ref "R159")
      (value "15K")
      (footprint "eagle-import:0207_10")
      (libsource (lib "eagle-import") (part "R-US_0207/10"))
    )
    (comp (ref "R160")
      (value "15K")
      (footprint "eagle-import:0207_10")
      (libsource (lib "eagle-import") (part "R-US_0207/10"))
    )
    (comp (ref "R161")
      (value "1800")
      (footprint "eagle-import:0207_10")
      (libsource (lib "eagle-import") (part "R-US_0207/10"))
    )
    (comp (ref "R162")
      (value "470")
      (footprint "eagle-import:0207_10")
      (libsource (lib "eagle-import") (part "R-US_0207/10"))
    )
    (comp (ref "R163")
      (value "27")
      (footprint "eagle-import:0207_10")
      (libsource (lib "eagle-import") (part "R-US_0207/10"))
    )
    (comp (ref "R164")
      (value "470")
      (footprint "eagle-import:0207_10")
      (libsource (lib "eagle-import") (part "R-US_0207/10"))
    )
    (comp (ref "R165")
      (value "27")
      (footprint "eagle-import:0207_10")
      (libsource (lib "eagle-import") (part "R-US_0207/10"))
    )
    (comp (ref "R166")
      (value "1K")
      (footprint "eagle-import:0207_10")
      (libsource (lib "eagle-import") (part "R-US_0207/10"))
    )
    (comp (ref "R167")
      (value "470")
      (footprint "eagle-import:0207_10")
      (libsource (lib "eagle-import") (part "R-US_0207/10"))
    )
    (comp (ref "R168")
      (value "1K")
      (footprint "eagle-import:0207_10")
      (libsource (lib "eagle-import") (part "R-US_0207/10"))
    )
    (comp (ref "R169")
      (value "100")
      (footprint "eagle-import:0207_10")
      (libsource (lib "eagle-import") (part "R-US_0207/10"))
    )
    (comp (ref "R170")
      (value "470")
      (footprint "eagle-import:0207_10")
      (libsource (lib "eagle-import") (part "R-US_0207/10"))
    )
    (comp (ref "R171")
      (value "4.7K")
      (footprint "eagle-import:0207_10")
      (libsource (lib "eagle-import") (part "R-US_0207/10"))
    )
    (comp (ref "R172")
      (value "27")
      (footprint "eagle-import:0207_10")
      (libsource (lib "eagle-import") (part "R-US_0207/10"))
    )
    (comp (ref "R173")
      (value "4.7K")
      (footprint "eagle-import:0207_10")
      (libsource (lib "eagle-import") (part "R-US_0207/10"))
    )
    (comp (ref "R174")
      (value "27")
      (footprint "eagle-import:0207_10")
      (libsource (lib "eagle-import") (part "R-US_0207/10"))
    )
    (comp (ref "R175")
      (value "470")
      (footprint "eagle-import:0204_7")
      (libsource (lib "eagle-import") (part "R-US_0204/7"))
    )
    (comp (ref "S1")
      (value "ROTARY8E")
      (footprint "eagle-import:ROTARY-8E")
      (libsource (lib "eagle-import") (part "ROTARY8E"))
    )
    (comp (ref "S11")
      (value "DPDT8I")
      (footprint "eagle-import:DPDT8I")
      (libsource (lib "eagle-import") (part "DPDT8I"))
    )
    (comp (ref "S12")
      (value "DPDT8I")
      (footprint "eagle-import:DPDT8I")
      (libsource (lib "eagle-import") (part "DPDT8I"))
    )
    (comp (ref "S13")
      (value "DPDT8I")
      (footprint "eagle-import:DPDT8I")
      (libsource (lib "eagle-import") (part "DPDT8I"))
    )
    (comp (ref "S14")
      (value "DPDT8I")
      (footprint "eagle-import:DPDT8I")
      (libsource (lib "eagle-import") (part "DPDT8I"))
    )
    (comp (ref "S15")
      (value "DPDT8I")
      (footprint "eagle-import:DPDT8I")
      (libsource (lib "eagle-import") (part "DPDT8I"))
    )
    (comp (ref "S16")
      (value "DPDT8I")
      (footprint "eagle-import:DPDT8I")
      (libsource (lib "eagle-import") (part "DPDT8I"))
    )
    (comp (ref "S17")
      (value "DPDT8I")
      (footprint "eagle-import:DPDT8I")
      (libsource (lib "eagle-import") (part "DPDT8I"))
    )
    (comp (ref "S18")
      (value "DPDT8I")
      (footprint "eagle-import:DPDT8I")
      (libsource (lib "eagle-import") (part "DPDT8I"))
    )
    (comp (ref "S19")
      (value "DPDT8I")
      (footprint "eagle-import:DPDT8I")
      (libsource (lib "eagle-import") (part "DPDT8I"))
    )
    (comp (ref "S20")
      (value "DPDT8I")
      (footprint "eagle-import:DPDT8I")
      (libsource (lib "eagle-import") (part "DPDT8I"))
    )
    (comp (ref "S21")
      (value "DPDT8I")
      (footprint "eagle-import:DPDT8I")
      (libsource (lib "eagle-import") (part "DPDT8I"))
    )
    (comp (ref "S22")
      (value "DPDT8I")
      (footprint "eagle-import:DPDT8I")
      (libsource (lib "eagle-import") (part "DPDT8I"))
    )
    (comp (ref "SSTP")
      (value "DPDT8I")
      (footprint "eagle-import:DPDT8I")
      (libsource (lib "eagle-import") (part "DPDT8I"))
    )
    (comp (ref "SW")
      (value "DPDT8I")
      (footprint "eagle-import:DPDT8I")
      (libsource (lib "eagle-import") (part "DPDT8I"))
    )
    (comp (ref "U$2")
      (value "QUAD")
      (footprint "eagle-import:EDGE-CON8")
      (libsource (lib "eagle-import") (part "QUAD"))
    )
    (comp (ref "W1")
      (value "W2")
      (footprint "eagle-import:0R2_10")
      (libsource (lib "eagle-import") (part "0R2"))
    )
    (comp (ref "YELLOW")
      (value "LUG")
      (footprint "eagle-import:SPADELUG")
      (libsource (lib "eagle-import") (part "LUG"))
    )
  )
  (nets
    (net (code "1") (name "+0.75V") (class "Default")
      (node (ref "D125") (pin "C") (pinfunction "C_C") (pintype "passive"))
      (node (ref "D126") (pin "A") (pinfunction "A_A") (pintype "passive"))
    )
    (net (code "2") (name "+3V3") (class "Default")
      (node (ref "D123") (pin "A") (pinfunction "A_A") (pintype "passive"))
      (node (ref "E11") (pin "14") (pinfunction "B3_14") (pintype "input"))
      (node (ref "E14") (pin "6") (pinfunction "A1_6") (pintype "input"))
      (node (ref "E3") (pin "13") (pinfunction "3_13") (pintype "input"))
      (node (ref "E3") (pin "2") (pinfunction "5_2") (pintype "input"))
      (node (ref "R170") (pin "1") (pinfunction "1_1") (pintype "passive"))
    )
    (net (code "3") (name "+8V") (class "Default")
      (node (ref "YELLOW") (pin "1") (pinfunction "1_1") (pintype "passive"))
    )
    (net (code "4") (name "-15V") (class "Default")
      (node (ref "I28") (pin "K") (pinfunction "C_K") (pintype "passive"))
      (node (ref "R158") (pin "1") (pinfunction "1_1") (pintype "passive"))
      (node (ref "R47") (pin "1") (pinfunction "1_1") (pintype "passive"))
      (node (ref "S11") (pin "L2") (pinfunction "A2_L2") (pintype "bidirectional"))
      (node (ref "S11") (pin "R2") (pinfunction "B2_R2") (pintype "bidirectional"))
      (node (ref "S12") (pin "L2") (pinfunction "A2_L2") (pintype "bidirectional"))
      (node (ref "S12") (pin "R2") (pinfunction "B2_R2") (pintype "bidirectional"))
      (node (ref "S13") (pin "L2") (pinfunction "A2_L2") (pintype "bidirectional"))
      (node (ref "S13") (pin "R2") (pinfunction "B2_R2") (pintype "bidirectional"))
      (node (ref "S14") (pin "L2") (pinfunction "A2_L2") (pintype "bidirectional"))
      (node (ref "S14") (pin "R2") (pinfunction "B2_R2") (pintype "bidirectional"))
      (node (ref "S15") (pin "L2") (pinfunction "A2_L2") (pintype "bidirectional"))
      (node (ref "S15") (pin "R2") (pinfunction "B2_R2") (pintype "bidirectional"))
      (node (ref "S16") (pin "L2") (pinfunction "A2_L2") (pintype "bidirectional"))
      (node (ref "S16") (pin "R2") (pinfunction "B2_R2") (pintype "bidirectional"))
      (node (ref "S17") (pin "L2") (pinfunction "A2_L2") (pintype "bidirectional"))
      (node (ref "S17") (pin "R2") (pinfunction "B2_R2") (pintype "bidirectional"))
      (node (ref "S18") (pin "L2") (pinfunction "A2_L2") (pintype "bidirectional"))
      (node (ref "S18") (pin "R2") (pinfunction "B2_R2") (pintype "bidirectional"))
      (node (ref "S19") (pin "L2") (pinfunction "A2_L2") (pintype "bidirectional"))
      (node (ref "S19") (pin "R2") (pinfunction "B2_R2") (pintype "bidirectional"))
      (node (ref "S20") (pin "L2") (pinfunction "A2_L2") (pintype "bidirectional"))
      (node (ref "S20") (pin "R2") (pinfunction "B2_R2") (pintype "bidirectional"))
      (node (ref "S21") (pin "L2") (pinfunction "A2_L2") (pintype "bidirectional"))
      (node (ref "S21") (pin "R2") (pinfunction "B2_R2") (pintype "bidirectional"))
      (node (ref "S22") (pin "L2") (pinfunction "A2_L2") (pintype "bidirectional"))
      (node (ref "S22") (pin "R2") (pinfunction "B2_R2") (pintype "bidirectional"))
      (node (ref "U$2") (pin "BB2") (pinfunction "1_BB2") (pintype "bidirectional"))
      (node (ref "U$2") (pin "CB2") (pinfunction "1_CB2") (pintype "bidirectional"))
      (node (ref "U$2") (pin "DB2") (pinfunction "1_DB2") (pintype "bidirectional"))
      (node (ref "W1") (pin "3") (pinfunction "3_3") (pintype "passive"))
    )
    (net (code "5") (name "AC_EN") (class "Default")
      (node (ref "E14") (pin "11") (pinfunction "B2_11") (pintype "input"))
      (node (ref "E14") (pin "14") (pinfunction "B3_14") (pintype "input"))
      (node (ref "R173") (pin "1") (pinfunction "1_1") (pintype "passive"))
      (node (ref "S1") (pin "4") (pinfunction "4_4") (pintype "passive"))
    )
    (net (code "6") (name "BK_DATA_CONT") (class "Default")
      (node (ref "E11") (pin "13") (pinfunction "F3_13") (pintype "open_collector"))
      (node (ref "U$2") (pin "BK2") (pinfunction "1_BK2") (pintype "bidirectional"))
    )
    (net (code "7") (name "BREAK_C") (class "Default")
      (node (ref "U$2") (pin "BL2") (pinfunction "1_BL2") (pintype "bidirectional"))
    )
    (net (code "8") (name "BRK_INP") (class "Default")
      (node (ref "U$2") (pin "BE2") (pinfunction "1_BE2") (pintype "bidirectional"))
    )
    (net (code "9") (name "BUS_EN") (class "Default")
      (node (ref "E14") (pin "5") (pinfunction "B1_5") (pintype "input"))
      (node (ref "R145") (pin "1") (pinfunction "1_1") (pintype "passive"))
      (node (ref "S1") (pin "1") (pinfunction "1_1") (pintype "passive"))
    )
    (net (code "10") (name "CLR") (class "Default")
      (node (ref "E20") (pin "13") (pinfunction "I3_13") (pintype "input"))
    )
    (net (code "11") (name "CONT") (class "Default")
      (node (ref "E6") (pin "5") (pinfunction "I2_5") (pintype "input"))
    )
    (net (code "12") (name "CP_START") (class "Default")
      (node (ref "E6") (pin "13") (pinfunction "I2_13") (pintype "input"))
    )
    (net (code "13") (name "D") (class "Default")
      (node (ref "U$2") (pin "DK2") (pinfunction "1_DK2") (pintype "bidirectional"))
    )
    (net (code "14") (name "DATA00") (class "Default")
      (node (ref "U$2") (pin "AR1") (pinfunction "1_AR1") (pintype "bidirectional"))
    )
    (net (code "15") (name "DATA01") (class "Default")
      (node (ref "U$2") (pin "AS1") (pinfunction "1_AS1") (pintype "bidirectional"))
    )
    (net (code "16") (name "DATA02") (class "Default")
      (node (ref "U$2") (pin "AU1") (pinfunction "1_AU1") (pintype "bidirectional"))
    )
    (net (code "17") (name "DATA03") (class "Default")
      (node (ref "U$2") (pin "AV1") (pinfunction "1_AV1") (pintype "bidirectional"))
    )
    (net (code "18") (name "DATA04") (class "Default")
      (node (ref "U$2") (pin "BR1") (pinfunction "1_BR1") (pintype "bidirectional"))
    )
    (net (code "19") (name "DATA05") (class "Default")
      (node (ref "U$2") (pin "BS1") (pinfunction "1_BS1") (pintype "bidirectional"))
    )
    (net (code "20") (name "DATA06") (class "Default")
      (node (ref "U$2") (pin "BU1") (pinfunction "1_BU1") (pintype "bidirectional"))
    )
    (net (code "21") (name "DATA07") (class "Default")
      (node (ref "U$2") (pin "BV1") (pinfunction "1_BV1") (pintype "bidirectional"))
    )
    (net (code "22") (name "DATA08") (class "Default")
      (node (ref "U$2") (pin "DR1") (pinfunction "1_DR1") (pintype "bidirectional"))
    )
    (net (code "23") (name "DATA09") (class "Default")
      (node (ref "U$2") (pin "DS1") (pinfunction "1_DS1") (pintype "bidirectional"))
    )
    (net (code "24") (name "DATA10") (class "Default")
      (node (ref "U$2") (pin "DU1") (pinfunction "1_DU1") (pintype "bidirectional"))
    )
    (net (code "25") (name "DATA11") (class "Default")
      (node (ref "U$2") (pin "DV1") (pinfunction "1_DV1") (pintype "bidirectional"))
    )
    (net (code "27") (name "DEP") (class "Default")
      (node (ref "E13") (pin "10") (pinfunction "I1_10") (pintype "input"))
      (node (ref "E6") (pin "3") (pinfunction "I0_3") (pintype "input"))
    )
    (net (code "28") (name "DEP+EXAM+CONT") (class "Default")
      (node (ref "E6") (pin "6") (pinfunction "O_6") (pintype "output"))
    )
    (net (code "29") (name "E") (class "Default")
      (node (ref "U$2") (pin "DL2") (pinfunction "1_DL2") (pintype "bidirectional"))
    )
    (net (code "30") (name "EMA0") (class "Default")
      (node (ref "E37") (pin "1") (pinfunction "I_1") (pintype "input"))
      (node (ref "U$2") (pin "AD2") (pinfunction "1_AD2") (pintype "bidirectional"))
    )
    (net (code "31") (name "EMA1") (class "Default")
      (node (ref "E37") (pin "3") (pinfunction "I_3") (pintype "input"))
      (node (ref "U$2") (pin "AE2") (pinfunction "1_AE2") (pintype "bidirectional"))
    )
    (net (code "32") (name "EMA2") (class "Default")
      (node (ref "E37") (pin "5") (pinfunction "I_5") (pintype "input"))
      (node (ref "U$2") (pin "AH2") (pinfunction "1_AH2") (pintype "bidirectional"))
    )
    (net (code "33") (name "EXAM") (class "Default")
      (node (ref "E13") (pin "4") (pinfunction "I0_4") (pintype "input"))
      (node (ref "E6") (pin "4") (pinfunction "I1_4") (pintype "input"))
    )
    (net (code "34") (name "EXT_LOAD") (class "Default")
      (node (ref "E11") (pin "2") (pinfunction "B0_2") (pintype "input"))
      (node (ref "E20") (pin "9") (pinfunction "I0_9") (pintype "input"))
    )
    (net (code "35") (name "FETCH") (class "Default")
      (node (ref "U$2") (pin "DJ2") (pinfunction "1_DJ2") (pintype "bidirectional"))
    )
    (net (code "36") (name "GND") (class "Default")
      (node (ref "C1") (pin "-") (pinfunction "-_-") (pintype "passive"))
      (node (ref "C10") (pin "2") (pinfunction "2_2") (pintype "passive"))
      (node (ref "C11") (pin "2") (pinfunction "2_2") (pintype "passive"))
      (node (ref "C12") (pin "2") (pinfunction "2_2") (pintype "passive"))
      (node (ref "C13") (pin "2") (pinfunction "2_2") (pintype "passive"))
      (node (ref "C14") (pin "2") (pinfunction "2_2") (pintype "passive"))
      (node (ref "C15") (pin "2") (pinfunction "2_2") (pintype "passive"))
      (node (ref "C16") (pin "2") (pinfunction "2_2") (pintype "passive"))
      (node (ref "C2") (pin "-") (pinfunction "-_-") (pintype "passive"))
      (node (ref "C21") (pin "2") (pinfunction "2_2") (pintype "passive"))
      (node (ref "C22") (pin "2") (pinfunction "2_2") (pintype "passive"))
      (node (ref "C23") (pin "2") (pinfunction "2_2") (pintype "passive"))
      (node (ref "C24") (pin "2") (pinfunction "2_2") (pintype "passive"))
      (node (ref "C25") (pin "2") (pinfunction "2_2") (pintype "passive"))
      (node (ref "C26") (pin "2") (pinfunction "2_2") (pintype "passive"))
      (node (ref "C27") (pin "2") (pinfunction "2_2") (pintype "passive"))
      (node (ref "C28") (pin "2") (pinfunction "2_2") (pintype "passive"))
      (node (ref "C29") (pin "2") (pinfunction "2_2") (pintype "passive"))
      (node (ref "C3") (pin "-") (pinfunction "-_-") (pintype "passive"))
      (node (ref "C30") (pin "2") (pinfunction "2_2") (pintype "passive"))
      (node (ref "C31") (pin "2") (pinfunction "2_2") (pintype "passive"))
      (node (ref "C32") (pin "2") (pinfunction "2_2") (pintype "passive"))
      (node (ref "C33") (pin "2") (pinfunction "2_2") (pintype "passive"))
      (node (ref "C4") (pin "-") (pinfunction "-_-") (pintype "passive"))
      (node (ref "C5") (pin "2") (pinfunction "2_2") (pintype "passive"))
      (node (ref "C6") (pin "2") (pinfunction "2_2") (pintype "passive"))
      (node (ref "C7") (pin "2") (pinfunction "2_2") (pintype "passive"))
      (node (ref "C8") (pin "2") (pinfunction "2_2") (pintype "passive"))
      (node (ref "C9") (pin "2") (pinfunction "2_2") (pintype "passive"))
      (node (ref "D1") (pin "A") (pinfunction "A_A") (pintype "passive"))
      (node (ref "D100") (pin "A") (pinfunction "A_A") (pintype "passive"))
      (node (ref "D101") (pin "A") (pinfunction "A_A") (pintype "passive"))
      (node (ref "D102") (pin "A") (pinfunction "A_A") (pintype "passive"))
      (node (ref "D103") (pin "A") (pinfunction "A_A") (pintype "passive"))
      (node (ref "D104") (pin "A") (pinfunction "A_A") (pintype "passive"))
      (node (ref "D105") (pin "A") (pinfunction "A_A") (pintype "passive"))
      (node (ref "D126") (pin "C") (pinfunction "C_C") (pintype "passive"))
      (node (ref "D2") (pin "A") (pinfunction "A_A") (pintype "passive"))
      (node (ref "D3") (pin "A") (pinfunction "A_A") (pintype "passive"))
      (node (ref "D4") (pin "A") (pinfunction "A_A") (pintype "passive"))
      (node (ref "D94") (pin "A") (pinfunction "A_A") (pintype "passive"))
      (node (ref "D95") (pin "A") (pinfunction "A_A") (pintype "passive"))
      (node (ref "D96") (pin "A") (pinfunction "A_A") (pintype "passive"))
      (node (ref "D97") (pin "A") (pinfunction "A_A") (pintype "passive"))
      (node (ref "D98") (pin "A") (pinfunction "A_A") (pintype "passive"))
      (node (ref "D99") (pin "A") (pinfunction "A_A") (pintype "passive"))
      (node (ref "DEP") (pin "A2") (pinfunction "A2_A2") (pintype "bidirectional"))
      (node (ref "E11") (pin "10") (pinfunction "A2_10") (pintype "input"))
      (node (ref "E14") (pin "1") (pinfunction "A0_1") (pintype "input"))
      (node (ref "E14") (pin "10") (pinfunction "A2_10") (pintype "input"))
      (node (ref "E14") (pin "15") (pinfunction "A3_15") (pintype "input"))
      (node (ref "E18") (pin "1") (pinfunction "A_1") (pintype "input"))
      (node (ref "E18") (pin "9") (pinfunction "A_9") (pintype "input"))
      (node (ref "E3") (pin "5") (pinfunction "EI_5") (pintype "input"))
      (node (ref "Q1") (pin "1") (pinfunction "E_1") (pintype "passive"))
      (node (ref "Q10") (pin "1") (pinfunction "E_1") (pintype "passive"))
      (node (ref "Q11") (pin "1") (pinfunction "E_1") (pintype "passive"))
      (node (ref "Q12") (pin "1") (pinfunction "E_1") (pintype "passive"))
      (node (ref "Q13") (pin "3") (pinfunction "C_3") (pintype "passive"))
      (node (ref "Q19") (pin "1") (pinfunction "E_1") (pintype "passive"))
      (node (ref "Q2") (pin "1") (pinfunction "E_1") (pintype "passive"))
      (node (ref "Q3") (pin "1") (pinfunction "E_1") (pintype "passive"))
      (node (ref "Q4") (pin "1") (pinfunction "E_1") (pintype "passive"))
      (node (ref "Q5") (pin "1") (pinfunction "E_1") (pintype "passive"))
      (node (ref "Q6") (pin "1") (pinfunction "E_1") (pintype "passive"))
      (node (ref "Q7") (pin "1") (pinfunction "E_1") (pintype "passive"))
      (node (ref "Q8") (pin "1") (pinfunction "E_1") (pintype "passive"))
      (node (ref "Q9") (pin "1") (pinfunction "E_1") (pintype "passive"))
      (node (ref "R157") (pin "1") (pinfunction "1_1") (pintype "passive"))
      (node (ref "R159") (pin "1") (pinfunction "1_1") (pintype "passive"))
      (node (ref "R160") (pin "1") (pinfunction "1_1") (pintype "passive"))
      (node (ref "R25") (pin "1") (pinfunction "1_1") (pintype "passive"))
      (node (ref "R28") (pin "1") (pinfunction "1_1") (pintype "passive"))
      (node (ref "R31") (pin "1") (pinfunction "1_1") (pintype "passive"))
      (node (ref "R34") (pin "1") (pinfunction "1_1") (pintype "passive"))
      (node (ref "R37") (pin "1") (pinfunction "1_1") (pintype "passive"))
      (node (ref "R40") (pin "1") (pinfunction "1_1") (pintype "passive"))
      (node (ref "R43") (pin "1") (pinfunction "1_1") (pintype "passive"))
      (node (ref "R52") (pin "1") (pinfunction "1_1") (pintype "passive"))
      (node (ref "R58") (pin "1") (pinfunction "1_1") (pintype "passive"))
      (node (ref "U$2") (pin "AC2") (pinfunction "1_AC2") (pintype "bidirectional"))
      (node (ref "U$2") (pin "AF1") (pinfunction "1_AF1") (pintype "bidirectional"))
      (node (ref "U$2") (pin "AF2") (pinfunction "1_AF2") (pintype "bidirectional"))
      (node (ref "U$2") (pin "AN1") (pinfunction "1_AN1") (pintype "bidirectional"))
      (node (ref "U$2") (pin "AN2") (pinfunction "1_AN2") (pintype "bidirectional"))
      (node (ref "U$2") (pin "AT1") (pinfunction "1_AT1") (pintype "bidirectional"))
      (node (ref "U$2") (pin "AT2") (pinfunction "1_AT2") (pintype "bidirectional"))
      (node (ref "U$2") (pin "BC1") (pinfunction "1_BC1") (pintype "bidirectional"))
      (node (ref "U$2") (pin "BC2") (pinfunction "1_BC2") (pintype "bidirectional"))
      (node (ref "U$2") (pin "BF1") (pinfunction "1_BF1") (pintype "bidirectional"))
      (node (ref "U$2") (pin "BF2") (pinfunction "1_BF2") (pintype "bidirectional"))
      (node (ref "U$2") (pin "BN1") (pinfunction "1_BN1") (pintype "bidirectional"))
      (node (ref "U$2") (pin "BN2") (pinfunction "1_BN2") (pintype "bidirectional"))
      (node (ref "U$2") (pin "BT1") (pinfunction "1_BT1") (pintype "bidirectional"))
      (node (ref "U$2") (pin "BT2") (pinfunction "1_BT2") (pintype "bidirectional"))
      (node (ref "U$2") (pin "CC1") (pinfunction "1_CC1") (pintype "bidirectional"))
      (node (ref "U$2") (pin "CC2") (pinfunction "1_CC2") (pintype "bidirectional"))
      (node (ref "U$2") (pin "CF1") (pinfunction "1_CF1") (pintype "bidirectional"))
      (node (ref "U$2") (pin "CF2") (pinfunction "1_CF2") (pintype "bidirectional"))
      (node (ref "U$2") (pin "CN1") (pinfunction "1_CN1") (pintype "bidirectional"))
      (node (ref "U$2") (pin "CN2") (pinfunction "1_CN2") (pintype "bidirectional"))
      (node (ref "U$2") (pin "CT1") (pinfunction "1_CT1") (pintype "bidirectional"))
      (node (ref "U$2") (pin "CT2") (pinfunction "1_CT2") (pintype "bidirectional"))
      (node (ref "U$2") (pin "DC1") (pinfunction "1_DC1") (pintype "bidirectional"))
      (node (ref "U$2") (pin "DC2") (pinfunction "1_DC2") (pintype "bidirectional"))
      (node (ref "U$2") (pin "DF1") (pinfunction "1_DF1") (pintype "bidirectional"))
      (node (ref "U$2") (pin "DF2") (pinfunction "1_DF2") (pintype "bidirectional"))
      (node (ref "U$2") (pin "DT1") (pinfunction "1_DT1") (pintype "bidirectional"))
      (node (ref "U$2") (pin "DT2") (pinfunction "1_DT2") (pintype "bidirectional"))
    )
    (net (code "37") (name "HALT") (class "Default")
      (node (ref "D2") (pin "C") (pinfunction "C_C") (pintype "passive"))
      (node (ref "E9") (pin "7") (pinfunction "I1_7") (pintype "input"))
      (node (ref "R49") (pin "2") (pinfunction "2_2") (pintype "passive"))
    )
    (net (code "38") (name "IND1") (class "Default")
      (node (ref "E14") (pin "12") (pinfunction "F2_12") (pintype "open_collector"))
      (node (ref "E14") (pin "4") (pinfunction "F1_4") (pintype "open_collector"))
      (node (ref "U$2") (pin "CU2") (pinfunction "1_CU2") (pintype "bidirectional"))
    )
    (net (code "39") (name "IND2") (class "Default")
      (node (ref "E14") (pin "13") (pinfunction "F3_13") (pintype "open_collector"))
      (node (ref "E14") (pin "3") (pinfunction "F0_3") (pintype "open_collector"))
      (node (ref "U$2") (pin "CV2") (pinfunction "1_CV2") (pintype "bidirectional"))
    )
    (net (code "40") (name "INDSTROBE") (class "Default")
      (node (ref "E12") (pin "4") (pinfunction "O_4") (pintype "output"))
    )
    (net (code "41") (name "INIT") (class "Default")
      (node (ref "Q18") (pin "1") (pinfunction "E_1") (pintype "passive"))
      (node (ref "U$2") (pin "CR1") (pinfunction "1_CR1") (pintype "bidirectional"))
    )
    (net (code "42") (name "IR0") (class "Default")
      (node (ref "E25") (pin "4") (pinfunction "I0_4") (pintype "input"))
      (node (ref "U$2") (pin "DD2") (pinfunction "1_DD2") (pintype "bidirectional"))
    )
    (net (code "43") (name "IR1") (class "Default")
      (node (ref "E25") (pin "5") (pinfunction "I1_5") (pintype "input"))
      (node (ref "U$2") (pin "DE2") (pinfunction "1_DE2") (pintype "bidirectional"))
    )
    (net (code "44") (name "IR2") (class "Default")
      (node (ref "E25") (pin "6") (pinfunction "I2_6") (pintype "input"))
      (node (ref "U$2") (pin "DH2") (pinfunction "1_DH2") (pintype "bidirectional"))
    )
    (net (code "45") (name "I{slash}O_PAUSE") (class "Default")
      (node (ref "U$2") (pin "CD1") (pinfunction "1_CD1") (pintype "bidirectional"))
    )
    (net (code "46") (name "KEY_CONTROL") (class "Default")
      (node (ref "E11") (pin "3") (pinfunction "F0_3") (pintype "open_collector"))
      (node (ref "U$2") (pin "DU2") (pinfunction "1_DU2") (pintype "bidirectional"))
    )
    (net (code "47") (name "LA_ENABLE") (class "Default")
      (node (ref "E11") (pin "12") (pinfunction "F2_12") (pintype "open_collector"))
      (node (ref "E12") (pin "5") (pinfunction "I_5") (pintype "input"))
      (node (ref "E14") (pin "7") (pinfunction "S1_7") (pintype "input"))
      (node (ref "U$2") (pin "BM2") (pinfunction "1_BM2") (pintype "bidirectional"))
    )
    (net (code "48") (name "LOAD") (class "Default")
      (node (ref "E13") (pin "5") (pinfunction "I1_5") (pintype "input"))
      (node (ref "E20") (pin "10") (pinfunction "I1_10") (pintype "input"))
    )
    (net (code "49") (name "MA00") (class "Default")
      (node (ref "E37") (pin "13") (pinfunction "I_13") (pintype "input"))
      (node (ref "U$2") (pin "AD1") (pinfunction "1_AD1") (pintype "bidirectional"))
    )
    (net (code "50") (name "MA01") (class "Default")
      (node (ref "E37") (pin "11") (pinfunction "I_11") (pintype "input"))
      (node (ref "U$2") (pin "AE1") (pinfunction "1_AE1") (pintype "bidirectional"))
    )
    (net (code "51") (name "MA02") (class "Default")
      (node (ref "E37") (pin "9") (pinfunction "I_9") (pintype "input"))
      (node (ref "U$2") (pin "AH1") (pinfunction "1_AH1") (pintype "bidirectional"))
    )
    (net (code "52") (name "MA03") (class "Default")
      (node (ref "E29") (pin "1") (pinfunction "I_1") (pintype "input"))
      (node (ref "U$2") (pin "AJ1") (pinfunction "1_AJ1") (pintype "bidirectional"))
    )
    (net (code "53") (name "MA04") (class "Default")
      (node (ref "E29") (pin "3") (pinfunction "I_3") (pintype "input"))
      (node (ref "U$2") (pin "BD1") (pinfunction "1_BD1") (pintype "bidirectional"))
    )
    (net (code "54") (name "MA05") (class "Default")
      (node (ref "E29") (pin "5") (pinfunction "I_5") (pintype "input"))
      (node (ref "U$2") (pin "BE1") (pinfunction "1_BE1") (pintype "bidirectional"))
    )
    (net (code "55") (name "MA06") (class "Default")
      (node (ref "E29") (pin "13") (pinfunction "I_13") (pintype "input"))
      (node (ref "U$2") (pin "BH1") (pinfunction "1_BH1") (pintype "bidirectional"))
    )
    (net (code "56") (name "MA07") (class "Default")
      (node (ref "E29") (pin "11") (pinfunction "I_11") (pintype "input"))
      (node (ref "U$2") (pin "BJ1") (pinfunction "1_BJ1") (pintype "bidirectional"))
    )
    (net (code "57") (name "MA08") (class "Default")
      (node (ref "E26") (pin "1") (pinfunction "I_1") (pintype "input"))
      (node (ref "U$2") (pin "DD1") (pinfunction "1_DD1") (pintype "bidirectional"))
    )
    (net (code "58") (name "MA09") (class "Default")
      (node (ref "E26") (pin "3") (pinfunction "I_3") (pintype "input"))
      (node (ref "U$2") (pin "DE1") (pinfunction "1_DE1") (pintype "bidirectional"))
    )
    (net (code "59") (name "MA10") (class "Default")
      (node (ref "E26") (pin "5") (pinfunction "I_5") (pintype "input"))
      (node (ref "U$2") (pin "DH1") (pinfunction "1_DH1") (pintype "bidirectional"))
    )
    (net (code "60") (name "MA11") (class "Default")
      (node (ref "E26") (pin "11") (pinfunction "I_11") (pintype "input"))
      (node (ref "U$2") (pin "DJ1") (pinfunction "1_DJ1") (pintype "bidirectional"))
    )
    (net (code "61") (name "MD00") (class "Default")
      (node (ref "U$2") (pin "AK1") (pinfunction "1_AK1") (pintype "bidirectional"))
    )
    (net (code "62") (name "MD01") (class "Default")
      (node (ref "U$2") (pin "AL1") (pinfunction "1_AL1") (pintype "bidirectional"))
    )
    (net (code "63") (name "MD02") (class "Default")
      (node (ref "U$2") (pin "AM1") (pinfunction "1_AM1") (pintype "bidirectional"))
    )
    (net (code "64") (name "MD03") (class "Default")
      (node (ref "E25") (pin "10") (pinfunction "I4_10") (pintype "input"))
      (node (ref "U$2") (pin "AP1") (pinfunction "1_AP1") (pintype "bidirectional"))
    )
    (net (code "65") (name "MD04") (class "Default")
      (node (ref "U$2") (pin "BK1") (pinfunction "1_BK1") (pintype "bidirectional"))
    )
    (net (code "66") (name "MD05") (class "Default")
      (node (ref "U$2") (pin "BL1") (pinfunction "1_BL1") (pintype "bidirectional"))
    )
    (net (code "67") (name "MD06") (class "Default")
      (node (ref "U$2") (pin "BM1") (pinfunction "1_BM1") (pintype "bidirectional"))
    )
    (net (code "68") (name "MD07") (class "Default")
      (node (ref "U$2") (pin "BP1") (pinfunction "1_BP1") (pintype "bidirectional"))
    )
    (net (code "69") (name "MD08") (class "Default")
      (node (ref "U$2") (pin "DK1") (pinfunction "1_DK1") (pintype "bidirectional"))
    )
    (net (code "70") (name "MD09") (class "Default")
      (node (ref "E25") (pin "9") (pinfunction "I3_9") (pintype "input"))
      (node (ref "U$2") (pin "DL1") (pinfunction "1_DL1") (pintype "bidirectional"))
    )
    (net (code "71") (name "MD10") (class "Default")
      (node (ref "U$2") (pin "DM1") (pinfunction "1_DM1") (pintype "bidirectional"))
    )
    (net (code "72") (name "MD11") (class "Default")
      (node (ref "U$2") (pin "DP1") (pinfunction "1_DP1") (pintype "bidirectional"))
    )
    (net (code "73") (name "MD_DIR_IN") (class "Default")
      (node (ref "U$2") (pin "AK2") (pinfunction "1_AK2") (pintype "bidirectional"))
    )
    (net (code "74") (name "MD_EN") (class "Default")
      (node (ref "R142") (pin "1") (pinfunction "1_1") (pintype "passive"))
      (node (ref "S1") (pin "3") (pinfunction "3_3") (pintype "passive"))
    )
    (net (code "75") (name "MEMSTART") (class "Default")
      (node (ref "E11") (pin "7") (pinfunction "S1_7") (pintype "input"))
    )
    (net (code "76") (name "MEM_START") (class "Default")
      (node (ref "U$2") (pin "AJ2") (pinfunction "1_AJ2") (pintype "bidirectional"))
    )
    (net (code "77") (name "MQ_EN") (class "Default")
      (node (ref "E14") (pin "2") (pinfunction "B0_2") (pintype "input"))
      (node (ref "R171") (pin "1") (pinfunction "1_1") (pintype "passive"))
      (node (ref "S1") (pin "2") (pinfunction "2_2") (pintype "passive"))
    )
    (net (code "78") (name "MS_DISABLE") (class "Default")
      (node (ref "E11") (pin "4") (pinfunction "F1_4") (pintype "open_collector"))
      (node (ref "U$2") (pin "CV1") (pinfunction "1_CV1") (pintype "bidirectional"))
    )
    (net (code "79") (name "Net-(C19-Pad1)") (class "Default")
      (node (ref "C19") (pin "1") (pinfunction "1_1") (pintype "passive"))
      (node (ref "R159") (pin "2") (pinfunction "2_2") (pintype "passive"))
      (node (ref "R160") (pin "2") (pinfunction "2_2") (pintype "passive"))
    )
    (net (code "80") (name "Net-(C20-Pad1)") (class "Default")
      (node (ref "C20") (pin "1") (pinfunction "1_1") (pintype "passive"))
      (node (ref "R161") (pin "1") (pinfunction "1_1") (pintype "passive"))
    )
    (net (code "81") (name "Net-(CLR-PadA1)") (class "Default")
      (node (ref "CLR") (pin "A1") (pinfunction "A1_A1") (pintype "bidirectional"))
      (node (ref "EXT_LD") (pin "A2") (pinfunction "A2_A2") (pintype "bidirectional"))
    )
    (net (code "82") (name "Net-(CLR-PadA2)") (class "Default")
      (node (ref "CLR") (pin "A2") (pinfunction "A2_A2") (pintype "bidirectional"))
      (node (ref "CONT") (pin "A1") (pinfunction "A1_A1") (pintype "bidirectional"))
    )
    (net (code "83") (name "Net-(CONT-PadA2)") (class "Default")
      (node (ref "CONT") (pin "A2") (pinfunction "A2_A2") (pintype "bidirectional"))
      (node (ref "EXAM") (pin "A1") (pinfunction "A1_A1") (pintype "bidirectional"))
    )
    (net (code "84") (name "Net-(D4-PadC)") (class "Default")
      (node (ref "D4") (pin "C") (pinfunction "C_C") (pintype "passive"))
      (node (ref "R47") (pin "2") (pinfunction "2_2") (pintype "passive"))
      (node (ref "S1") (pin "S") (pinfunction "S_S") (pintype "passive"))
    )
    (net (code "85") (name "Net-(D5-PadA)") (class "Default")
      (node (ref "D5") (pin "A") (pinfunction "A_A") (pintype "passive"))
      (node (ref "R38") (pin "2") (pinfunction "2_2") (pintype "passive"))
    )
    (net (code "86") (name "Net-(D6-PadA)") (class "Default")
      (node (ref "D6") (pin "A") (pinfunction "A_A") (pintype "passive"))
      (node (ref "R41") (pin "2") (pinfunction "2_2") (pintype "passive"))
    )
    (net (code "87") (name "Net-(D8-C)") (class "Default")
      (node (ref "D8") (pin "K") (pinfunction "C_K") (pintype "passive"))
      (node (ref "E37") (pin "2") (pinfunction "O_2") (pintype "open_collector"))
    )
    (net (code "88") (name "Net-(D8-PadA)") (class "Default")
      (node (ref "D8") (pin "A") (pinfunction "A_A") (pintype "passive"))
      (node (ref "R7") (pin "1") (pinfunction "1_1") (pintype "passive"))
    )
    (net (code "89") (name "Net-(D9-C)") (class "Default")
      (node (ref "D9") (pin "K") (pinfunction "C_K") (pintype "passive"))
      (node (ref "E37") (pin "4") (pinfunction "O_4") (pintype "open_collector"))
    )
    (net (code "90") (name "Net-(D9-PadA)") (class "Default")
      (node (ref "D9") (pin "A") (pinfunction "A_A") (pintype "passive"))
      (node (ref "R8") (pin "1") (pinfunction "1_1") (pintype "passive"))
    )
    (net (code "91") (name "Net-(D10-C)") (class "Default")
      (node (ref "D10") (pin "K") (pinfunction "C_K") (pintype "passive"))
      (node (ref "E37") (pin "6") (pinfunction "O_6") (pintype "open_collector"))
    )
    (net (code "92") (name "Net-(D10-PadA)") (class "Default")
      (node (ref "D10") (pin "A") (pinfunction "A_A") (pintype "passive"))
      (node (ref "R9") (pin "1") (pinfunction "1_1") (pintype "passive"))
    )
    (net (code "93") (name "Net-(D11-C)") (class "Default")
      (node (ref "D11") (pin "K") (pinfunction "C_K") (pintype "passive"))
      (node (ref "E37") (pin "12") (pinfunction "O_12") (pintype "open_collector"))
    )
    (net (code "94") (name "Net-(D11-PadA)") (class "Default")
      (node (ref "D11") (pin "A") (pinfunction "A_A") (pintype "passive"))
      (node (ref "R10") (pin "1") (pinfunction "1_1") (pintype "passive"))
    )
    (net (code "95") (name "Net-(D12-C)") (class "Default")
      (node (ref "D12") (pin "K") (pinfunction "C_K") (pintype "passive"))
      (node (ref "E37") (pin "10") (pinfunction "O_10") (pintype "open_collector"))
    )
    (net (code "96") (name "Net-(D12-PadA)") (class "Default")
      (node (ref "D12") (pin "A") (pinfunction "A_A") (pintype "passive"))
      (node (ref "R11") (pin "1") (pinfunction "1_1") (pintype "passive"))
    )
    (net (code "97") (name "Net-(D13-C)") (class "Default")
      (node (ref "D13") (pin "K") (pinfunction "C_K") (pintype "passive"))
      (node (ref "E37") (pin "8") (pinfunction "O_8") (pintype "open_collector"))
    )
    (net (code "98") (name "Net-(D13-PadA)") (class "Default")
      (node (ref "D13") (pin "A") (pinfunction "A_A") (pintype "passive"))
      (node (ref "R12") (pin "1") (pinfunction "1_1") (pintype "passive"))
    )
    (net (code "99") (name "Net-(D14-C)") (class "Default")
      (node (ref "D14") (pin "K") (pinfunction "C_K") (pintype "passive"))
      (node (ref "E29") (pin "2") (pinfunction "O_2") (pintype "open_collector"))
    )
    (net (code "100") (name "Net-(D14-PadA)") (class "Default")
      (node (ref "D14") (pin "A") (pinfunction "A_A") (pintype "passive"))
      (node (ref "R13") (pin "1") (pinfunction "1_1") (pintype "passive"))
    )
    (net (code "101") (name "Net-(D15-C)") (class "Default")
      (node (ref "D15") (pin "K") (pinfunction "C_K") (pintype "passive"))
      (node (ref "E29") (pin "4") (pinfunction "O_4") (pintype "open_collector"))
    )
    (net (code "102") (name "Net-(D15-PadA)") (class "Default")
      (node (ref "D15") (pin "A") (pinfunction "A_A") (pintype "passive"))
      (node (ref "R14") (pin "1") (pinfunction "1_1") (pintype "passive"))
    )
    (net (code "103") (name "Net-(D16-C)") (class "Default")
      (node (ref "D16") (pin "K") (pinfunction "C_K") (pintype "passive"))
      (node (ref "E29") (pin "6") (pinfunction "O_6") (pintype "open_collector"))
    )
    (net (code "104") (name "Net-(D16-PadA)") (class "Default")
      (node (ref "D16") (pin "A") (pinfunction "A_A") (pintype "passive"))
      (node (ref "R15") (pin "1") (pinfunction "1_1") (pintype "passive"))
    )
    (net (code "105") (name "Net-(D17-C)") (class "Default")
      (node (ref "D17") (pin "K") (pinfunction "C_K") (pintype "passive"))
      (node (ref "E29") (pin "12") (pinfunction "O_12") (pintype "open_collector"))
    )
    (net (code "106") (name "Net-(D17-PadA)") (class "Default")
      (node (ref "D17") (pin "A") (pinfunction "A_A") (pintype "passive"))
      (node (ref "R16") (pin "1") (pinfunction "1_1") (pintype "passive"))
    )
    (net (code "107") (name "Net-(D18-C)") (class "Default")
      (node (ref "D18") (pin "K") (pinfunction "C_K") (pintype "passive"))
      (node (ref "E29") (pin "10") (pinfunction "O_10") (pintype "open_collector"))
    )
    (net (code "108") (name "Net-(D18-PadA)") (class "Default")
      (node (ref "D18") (pin "A") (pinfunction "A_A") (pintype "passive"))
      (node (ref "R17") (pin "1") (pinfunction "1_1") (pintype "passive"))
    )
    (net (code "109") (name "Net-(D19-C)") (class "Default")
      (node (ref "D19") (pin "K") (pinfunction "C_K") (pintype "passive"))
      (node (ref "E26") (pin "2") (pinfunction "O_2") (pintype "open_collector"))
    )
    (net (code "110") (name "Net-(D19-PadA)") (class "Default")
      (node (ref "D19") (pin "A") (pinfunction "A_A") (pintype "passive"))
      (node (ref "R18") (pin "1") (pinfunction "1_1") (pintype "passive"))
    )
    (net (code "111") (name "Net-(D20-C)") (class "Default")
      (node (ref "D20") (pin "K") (pinfunction "C_K") (pintype "passive"))
      (node (ref "E26") (pin "4") (pinfunction "O_4") (pintype "open_collector"))
    )
    (net (code "112") (name "Net-(D20-PadA)") (class "Default")
      (node (ref "D20") (pin "A") (pinfunction "A_A") (pintype "passive"))
      (node (ref "R19") (pin "1") (pinfunction "1_1") (pintype "passive"))
    )
    (net (code "113") (name "Net-(D21-C)") (class "Default")
      (node (ref "D21") (pin "K") (pinfunction "C_K") (pintype "passive"))
      (node (ref "E26") (pin "6") (pinfunction "O_6") (pintype "open_collector"))
    )
    (net (code "114") (name "Net-(D21-PadA)") (class "Default")
      (node (ref "D21") (pin "A") (pinfunction "A_A") (pintype "passive"))
      (node (ref "R20") (pin "1") (pinfunction "1_1") (pintype "passive"))
    )
    (net (code "115") (name "Net-(D22-C)") (class "Default")
      (node (ref "D22") (pin "K") (pinfunction "C_K") (pintype "passive"))
      (node (ref "E26") (pin "10") (pinfunction "O_10") (pintype "open_collector"))
    )
    (net (code "116") (name "Net-(D22-PadA)") (class "Default")
      (node (ref "D22") (pin "A") (pinfunction "A_A") (pintype "passive"))
      (node (ref "R21") (pin "1") (pinfunction "1_1") (pintype "passive"))
    )
    (net (code "117") (name "Net-(D94-PadC)") (class "Default")
      (node (ref "D94") (pin "C") (pinfunction "C_C") (pintype "passive"))
      (node (ref "R103") (pin "2") (pinfunction "2_2") (pintype "passive"))
    )
    (net (code "118") (name "Net-(D95-PadC)") (class "Default")
      (node (ref "D95") (pin "C") (pinfunction "C_C") (pintype "passive"))
      (node (ref "R105") (pin "2") (pinfunction "2_2") (pintype "passive"))
    )
    (net (code "119") (name "Net-(D96-PadC)") (class "Default")
      (node (ref "D96") (pin "C") (pinfunction "C_C") (pintype "passive"))
      (node (ref "R107") (pin "2") (pinfunction "2_2") (pintype "passive"))
    )
    (net (code "120") (name "Net-(D97-PadC)") (class "Default")
      (node (ref "D97") (pin "C") (pinfunction "C_C") (pintype "passive"))
      (node (ref "R109") (pin "2") (pinfunction "2_2") (pintype "passive"))
    )
    (net (code "121") (name "Net-(D98-PadC)") (class "Default")
      (node (ref "D98") (pin "C") (pinfunction "C_C") (pintype "passive"))
      (node (ref "R111") (pin "2") (pinfunction "2_2") (pintype "passive"))
    )
    (net (code "122") (name "Net-(D99-PadC)") (class "Default")
      (node (ref "D99") (pin "C") (pinfunction "C_C") (pintype "passive"))
      (node (ref "R113") (pin "2") (pinfunction "2_2") (pintype "passive"))
    )
    (net (code "123") (name "Net-(D100-PadC)") (class "Default")
      (node (ref "D100") (pin "C") (pinfunction "C_C") (pintype "passive"))
      (node (ref "R115") (pin "2") (pinfunction "2_2") (pintype "passive"))
    )
    (net (code "124") (name "Net-(D101-PadC)") (class "Default")
      (node (ref "D101") (pin "C") (pinfunction "C_C") (pintype "passive"))
      (node (ref "R117") (pin "2") (pinfunction "2_2") (pintype "passive"))
    )
    (net (code "125") (name "Net-(D102-PadC)") (class "Default")
      (node (ref "D102") (pin "C") (pinfunction "C_C") (pintype "passive"))
      (node (ref "R119") (pin "2") (pinfunction "2_2") (pintype "passive"))
    )
    (net (code "126") (name "Net-(D103-PadC)") (class "Default")
      (node (ref "D103") (pin "C") (pinfunction "C_C") (pintype "passive"))
      (node (ref "R121") (pin "2") (pinfunction "2_2") (pintype "passive"))
    )
    (net (code "127") (name "Net-(D104-PadC)") (class "Default")
      (node (ref "D104") (pin "C") (pinfunction "C_C") (pintype "passive"))
      (node (ref "R123") (pin "2") (pinfunction "2_2") (pintype "passive"))
    )
    (net (code "128") (name "Net-(D105-PadC)") (class "Default")
      (node (ref "D105") (pin "C") (pinfunction "C_C") (pintype "passive"))
      (node (ref "R125") (pin "2") (pinfunction "2_2") (pintype "passive"))
    )
    (net (code "129") (name "Net-(D122-PadA)") (class "Default")
      (node (ref "D122") (pin "A") (pinfunction "A_A") (pintype "passive"))
      (node (ref "R169") (pin "2") (pinfunction "2_2") (pintype "passive"))
    )
    (net (code "130") (name "Net-(D123-PadC)") (class "Default")
      (node (ref "D123") (pin "C") (pinfunction "C_C") (pintype "passive"))
      (node (ref "D124") (pin "A") (pinfunction "A_A") (pintype "passive"))
    )
    (net (code "131") (name "Net-(D124-PadC)") (class "Default")
      (node (ref "D124") (pin "C") (pinfunction "C_C") (pintype "passive"))
      (node (ref "D125") (pin "A") (pinfunction "A_A") (pintype "passive"))
    )
    (net (code "132") (name "Net-(DEP-PadA1)") (class "Default")
      (node (ref "DEP") (pin "A1") (pinfunction "A1_A1") (pintype "bidirectional"))
      (node (ref "EXAM") (pin "A2") (pinfunction "A2_A2") (pintype "bidirectional"))
    )
    (net (code "133") (name "Net-(E1A-CLK)") (class "Default")
      (node (ref "E1") (pin "12") (pinfunction "D3_12") (pintype "input"))
      (node (ref "E1") (pin "13") (pinfunction "D4_13") (pintype "input"))
      (node (ref "E1") (pin "4") (pinfunction "D1_4") (pintype "input"))
      (node (ref "E1") (pin "5") (pinfunction "D2_5") (pintype "input"))
      (node (ref "E1") (pin "9") (pinfunction "CLK_9") (pintype "input"))
    )
    (net (code "134") (name "Net-(E1A-CLR)") (class "Default")
      (node (ref "E1") (pin "1") (pinfunction "CLR_1") (pintype "input"))
      (node (ref "E2") (pin "1") (pinfunction "CLR_1") (pintype "input"))
      (node (ref "E4") (pin "13") (pinfunction "CLR_13") (pintype "input"))
      (node (ref "LOAD") (pin "A1") (pinfunction "A1_A1") (pintype "bidirectional"))
      (node (ref "R39") (pin "1") (pinfunction "1_1") (pintype "passive"))
    )
    (net (code "135") (name "Net-(E1A-Q1)") (class "Default")
      (node (ref "E1") (pin "2") (pinfunction "Q1_2") (pintype "output"))
      (node (ref "E7") (pin "9") (pinfunction "I_9") (pintype "input"))
    )
    (net (code "136") (name "Net-(E1A-Q2)") (class "Default")
      (node (ref "E1") (pin "7") (pinfunction "Q2_7") (pintype "output"))
      (node (ref "E7") (pin "11") (pinfunction "I_11") (pintype "input"))
    )
    (net (code "137") (name "Net-(E1A-~{Q1})") (class "Default")
      (node (ref "E1") (pin "3") (pinfunction "~{Q1}_3") (pintype "output"))
      (node (ref "LOAD") (pin "A3") (pinfunction "A3_A3") (pintype "bidirectional"))
    )
    (net (code "138") (name "Net-(E1A-~{Q2})") (class "Default")
      (node (ref "E1") (pin "6") (pinfunction "~{Q2}_6") (pintype "output"))
      (node (ref "EXT_LD") (pin "A3") (pinfunction "A3_A3") (pintype "bidirectional"))
    )
    (net (code "139") (name "Net-(E2A-CLK)") (class "Default")
      (node (ref "E2") (pin "12") (pinfunction "D3_12") (pintype "input"))
      (node (ref "E2") (pin "13") (pinfunction "D4_13") (pintype "input"))
      (node (ref "E2") (pin "4") (pinfunction "D1_4") (pintype "input"))
      (node (ref "E2") (pin "5") (pinfunction "D2_5") (pintype "input"))
      (node (ref "E2") (pin "9") (pinfunction "CLK_9") (pintype "input"))
    )
    (net (code "140") (name "Net-(E2A-Q1)") (class "Default")
      (node (ref "E2") (pin "2") (pinfunction "Q1_2") (pintype "output"))
      (node (ref "E7") (pin "13") (pinfunction "I_13") (pintype "input"))
    )
    (net (code "141") (name "Net-(E2A-Q2)") (class "Default")
      (node (ref "E2") (pin "7") (pinfunction "Q2_7") (pintype "output"))
      (node (ref "E7") (pin "1") (pinfunction "I_1") (pintype "input"))
    )
    (net (code "142") (name "Net-(E2A-Q3)") (class "Default")
      (node (ref "E2") (pin "10") (pinfunction "Q3_10") (pintype "output"))
      (node (ref "E7") (pin "3") (pinfunction "I_3") (pintype "input"))
    )
    (net (code "143") (name "Net-(E2A-Q4)") (class "Default")
      (node (ref "E2") (pin "15") (pinfunction "Q4_15") (pintype "output"))
      (node (ref "E7") (pin "5") (pinfunction "I_5") (pintype "input"))
    )
    (net (code "144") (name "Net-(E2A-~{Q1})") (class "Default")
      (node (ref "CLR") (pin "A3") (pinfunction "A3_A3") (pintype "bidirectional"))
      (node (ref "E2") (pin "3") (pinfunction "~{Q1}_3") (pintype "output"))
    )
    (net (code "145") (name "Net-(E2A-~{Q2})") (class "Default")
      (node (ref "CONT") (pin "A3") (pinfunction "A3_A3") (pintype "bidirectional"))
      (node (ref "E2") (pin "6") (pinfunction "~{Q2}_6") (pintype "output"))
    )
    (net (code "146") (name "Net-(E2A-~{Q3})") (class "Default")
      (node (ref "E2") (pin "11") (pinfunction "~{Q3}_11") (pintype "output"))
      (node (ref "EXAM") (pin "A3") (pinfunction "A3_A3") (pintype "bidirectional"))
    )
    (net (code "147") (name "Net-(E2A-~{Q4})") (class "Default")
      (node (ref "DEP") (pin "A3") (pinfunction "A3_A3") (pintype "bidirectional"))
      (node (ref "E2") (pin "14") (pinfunction "~{Q4}_14") (pintype "output"))
    )
    (net (code "148") (name "Net-(E3A-E0)") (class "Default")
      (node (ref "E3") (pin "15") (pinfunction "E0_15") (pintype "output"))
      (node (ref "E4") (pin "11") (pinfunction "CLK_11") (pintype "input"))
    )
    (net (code "149") (name "Net-(E6C-I0)") (class "Default")
      (node (ref "E6") (pin "9") (pinfunction "I0_9") (pintype "input"))
      (node (ref "R147") (pin "1") (pinfunction "1_1") (pintype "passive"))
      (node (ref "R148") (pin "2") (pinfunction "2_2") (pintype "passive"))
    )
    (net (code "150") (name "Net-(E6C-I1)") (class "Default")
      (node (ref "E6") (pin "10") (pinfunction "I1_10") (pintype "input"))
      (node (ref "R146") (pin "1") (pinfunction "1_1") (pintype "passive"))
      (node (ref "R171") (pin "2") (pinfunction "2_2") (pintype "passive"))
    )
    (net (code "151") (name "Net-(E6C-I2)") (class "Default")
      (node (ref "E6") (pin "11") (pinfunction "I2_11") (pintype "input"))
      (node (ref "R144") (pin "1") (pinfunction "1_1") (pintype "passive"))
      (node (ref "R173") (pin "2") (pinfunction "2_2") (pintype "passive"))
    )
    (net (code "152") (name "Net-(E10C-I0)") (class "Default")
      (node (ref "E10") (pin "8") (pinfunction "I0_8") (pintype "input"))
      (node (ref "E10") (pin "9") (pinfunction "I1_9") (pintype "input"))
      (node (ref "E13") (pin "3") (pinfunction "O_3") (pintype "output"))
    )
    (net (code "153") (name "Net-(E11A-A0)") (class "Default")
      (node (ref "E11") (pin "1") (pinfunction "A0_1") (pintype "input"))
      (node (ref "E11") (pin "6") (pinfunction "A1_6") (pintype "input"))
    )
    (net (code "154") (name "Net-(E11A-A3)") (class "Default")
      (node (ref "E11") (pin "15") (pinfunction "A3_15") (pintype "input"))
      (node (ref "E12") (pin "12") (pinfunction "O_12") (pintype "output"))
    )
    (net (code "155") (name "Net-(E11A-B1)") (class "Default")
      (node (ref "E11") (pin "11") (pinfunction "B2_11") (pintype "input"))
      (node (ref "E11") (pin "5") (pinfunction "B1_5") (pintype "input"))
      (node (ref "E11") (pin "9") (pinfunction "S0_9") (pintype "input"))
    )
    (net (code "156") (name "Net-(E12A-O)") (class "Default")
      (node (ref "E12") (pin "2") (pinfunction "O_2") (pintype "output"))
      (node (ref "R166") (pin "1") (pinfunction "1_1") (pintype "passive"))
    )
    (net (code "157") (name "Net-(E12C-O)") (class "Default")
      (node (ref "E12") (pin "6") (pinfunction "O_6") (pintype "output"))
      (node (ref "E14") (pin "9") (pinfunction "S0_9") (pintype "input"))
    )
    (net (code "158") (name "Net-(E12E-I)") (class "Default")
      (node (ref "E12") (pin "11") (pinfunction "I_11") (pintype "input"))
      (node (ref "R152") (pin "1") (pinfunction "1_1") (pintype "passive"))
    )
    (net (code "159") (name "Net-(E13A-I1)") (class "Default")
      (node (ref "E13") (pin "2") (pinfunction "I1_2") (pintype "input"))
      (node (ref "E9") (pin "2") (pinfunction "O_2") (pintype "output"))
    )
    (net (code "160") (name "Net-(E13D-I1)") (class "Default")
      (node (ref "E13") (pin "13") (pinfunction "I1_13") (pintype "input"))
      (node (ref "E25") (pin "3") (pinfunction "O_3") (pintype "output"))
    )
    (net (code "161") (name "Net-(E13D-O)") (class "Default")
      (node (ref "E13") (pin "11") (pinfunction "O_11") (pintype "output"))
      (node (ref "E20") (pin "1") (pinfunction "I0_1") (pintype "input"))
      (node (ref "E20") (pin "2") (pinfunction "I1_2") (pintype "input"))
    )
    (net (code "162") (name "Net-(E18A-~{Q})") (class "Default")
      (node (ref "E18") (pin "10") (pinfunction "B_10") (pintype "input"))
      (node (ref "E18") (pin "4") (pinfunction "~{Q}_4") (pintype "output"))
    )
    (net (code "163") (name "Net-(E20A-I2)") (class "Default")
      (node (ref "E20") (pin "4") (pinfunction "I2_4") (pintype "input"))
      (node (ref "E20") (pin "5") (pinfunction "I3_5") (pintype "input"))
    )
    (net (code "164") (name "Net-(EXT_LD-PadA1)") (class "Default")
      (node (ref "EXT_LD") (pin "A1") (pinfunction "A1_A1") (pintype "bidirectional"))
      (node (ref "LOAD") (pin "A2") (pinfunction "A2_A2") (pintype "bidirectional"))
    )
    (net (code "165") (name "Net-(HALT-A1)") (class "Default")
      (node (ref "HALT") (pin "L1") (pinfunction "A1_L1") (pintype "bidirectional"))
      (node (ref "HALT") (pin "R1") (pinfunction "B1_R1") (pintype "bidirectional"))
      (node (ref "R49") (pin "1") (pinfunction "1_1") (pintype "passive"))
      (node (ref "R55") (pin "1") (pinfunction "1_1") (pintype "passive"))
    )
    (net (code "166") (name "Net-(I1-C)") (class "Default")
      (node (ref "I1") (pin "K") (pinfunction "C_K") (pintype "passive"))
      (node (ref "Q1") (pin "3") (pinfunction "C_3") (pintype "passive"))
      (node (ref "R25") (pin "2") (pinfunction "2_2") (pintype "passive"))
    )
    (net (code "167") (name "Net-(I2-C)") (class "Default")
      (node (ref "I2") (pin "K") (pinfunction "C_K") (pintype "passive"))
      (node (ref "Q2") (pin "3") (pinfunction "C_3") (pintype "passive"))
      (node (ref "R28") (pin "2") (pinfunction "2_2") (pintype "passive"))
    )
    (net (code "168") (name "Net-(I3-C)") (class "Default")
      (node (ref "I3") (pin "K") (pinfunction "C_K") (pintype "passive"))
      (node (ref "Q3") (pin "3") (pinfunction "C_3") (pintype "passive"))
      (node (ref "R31") (pin "2") (pinfunction "2_2") (pintype "passive"))
    )
    (net (code "169") (name "Net-(I4-C)") (class "Default")
      (node (ref "I4") (pin "K") (pinfunction "C_K") (pintype "passive"))
      (node (ref "Q4") (pin "3") (pinfunction "C_3") (pintype "passive"))
      (node (ref "R34") (pin "2") (pinfunction "2_2") (pintype "passive"))
    )
    (net (code "170") (name "Net-(I5-C)") (class "Default")
      (node (ref "I5") (pin "K") (pinfunction "C_K") (pintype "passive"))
      (node (ref "Q5") (pin "3") (pinfunction "C_3") (pintype "passive"))
      (node (ref "R37") (pin "2") (pinfunction "2_2") (pintype "passive"))
    )
    (net (code "171") (name "Net-(I6-C)") (class "Default")
      (node (ref "I6") (pin "K") (pinfunction "C_K") (pintype "passive"))
      (node (ref "Q6") (pin "3") (pinfunction "C_3") (pintype "passive"))
      (node (ref "R40") (pin "2") (pinfunction "2_2") (pintype "passive"))
    )
    (net (code "172") (name "Net-(I7-C)") (class "Default")
      (node (ref "I7") (pin "K") (pinfunction "C_K") (pintype "passive"))
      (node (ref "Q7") (pin "3") (pinfunction "C_3") (pintype "passive"))
      (node (ref "R43") (pin "2") (pinfunction "2_2") (pintype "passive"))
    )
    (net (code "173") (name "Net-(I8-C)") (class "Default")
      (node (ref "I8") (pin "K") (pinfunction "C_K") (pintype "passive"))
      (node (ref "Q8") (pin "3") (pinfunction "C_3") (pintype "passive"))
    )
    (net (code "174") (name "Net-(I9-C)") (class "Default")
      (node (ref "I9") (pin "K") (pinfunction "C_K") (pintype "passive"))
      (node (ref "Q9") (pin "3") (pinfunction "C_3") (pintype "passive"))
    )
    (net (code "175") (name "Net-(I10-C)") (class "Default")
      (node (ref "I10") (pin "K") (pinfunction "C_K") (pintype "passive"))
      (node (ref "Q10") (pin "3") (pinfunction "C_3") (pintype "passive"))
      (node (ref "R52") (pin "2") (pinfunction "2_2") (pintype "passive"))
    )
    (net (code "176") (name "Net-(I11-C)") (class "Default")
      (node (ref "I11") (pin "K") (pinfunction "C_K") (pintype "passive"))
      (node (ref "Q11") (pin "3") (pinfunction "C_3") (pintype "passive"))
    )
    (net (code "177") (name "Net-(I12-C)") (class "Default")
      (node (ref "I12") (pin "K") (pinfunction "C_K") (pintype "passive"))
      (node (ref "Q12") (pin "3") (pinfunction "C_3") (pintype "passive"))
      (node (ref "R58") (pin "2") (pinfunction "2_2") (pintype "passive"))
    )
    (net (code "178") (name "Net-(Q1-B)") (class "Default")
      (node (ref "Q1") (pin "2") (pinfunction "B_2") (pintype "passive"))
      (node (ref "R27") (pin "2") (pinfunction "2_2") (pintype "passive"))
    )
    (net (code "179") (name "Net-(Q2-B)") (class "Default")
      (node (ref "Q2") (pin "2") (pinfunction "B_2") (pintype "passive"))
      (node (ref "R30") (pin "2") (pinfunction "2_2") (pintype "passive"))
    )
    (net (code "180") (name "Net-(Q3-B)") (class "Default")
      (node (ref "Q3") (pin "2") (pinfunction "B_2") (pintype "passive"))
      (node (ref "R33") (pin "2") (pinfunction "2_2") (pintype "passive"))
    )
    (net (code "181") (name "Net-(Q4-B)") (class "Default")
      (node (ref "Q4") (pin "2") (pinfunction "B_2") (pintype "passive"))
      (node (ref "R36") (pin "2") (pinfunction "2_2") (pintype "passive"))
    )
    (net (code "182") (name "Net-(Q5-B)") (class "Default")
      (node (ref "D5") (pin "C") (pinfunction "C_C") (pintype "passive"))
      (node (ref "Q5") (pin "2") (pinfunction "B_2") (pintype "passive"))
    )
    (net (code "183") (name "Net-(Q6-B)") (class "Default")
      (node (ref "D6") (pin "C") (pinfunction "C_C") (pintype "passive"))
      (node (ref "Q6") (pin "2") (pinfunction "B_2") (pintype "passive"))
      (node (ref "R42") (pin "2") (pinfunction "2_2") (pintype "passive"))
    )
    (net (code "184") (name "Net-(Q9-B)") (class "Default")
      (node (ref "Q9") (pin "2") (pinfunction "B_2") (pintype "passive"))
      (node (ref "R51") (pin "2") (pinfunction "2_2") (pintype "passive"))
    )
    (net (code "185") (name "Net-(Q10-B)") (class "Default")
      (node (ref "Q10") (pin "2") (pinfunction "B_2") (pintype "passive"))
      (node (ref "R54") (pin "2") (pinfunction "2_2") (pintype "passive"))
    )
    (net (code "186") (name "Net-(Q11-B)") (class "Default")
      (node (ref "Q11") (pin "2") (pinfunction "B_2") (pintype "passive"))
      (node (ref "R57") (pin "2") (pinfunction "2_2") (pintype "passive"))
    )
    (net (code "187") (name "Net-(Q12-B)") (class "Default")
      (node (ref "Q12") (pin "2") (pinfunction "B_2") (pintype "passive"))
      (node (ref "R60") (pin "2") (pinfunction "2_2") (pintype "passive"))
    )
    (net (code "188") (name "Net-(Q13-B)") (class "Default")
      (node (ref "Q13") (pin "2") (pinfunction "B_2") (pintype "passive"))
      (node (ref "R154") (pin "2") (pinfunction "2_2") (pintype "passive"))
    )
    (net (code "189") (name "Net-(Q13-E)") (class "Default")
      (node (ref "Q13") (pin "1") (pinfunction "E_1") (pintype "passive"))
      (node (ref "Q14") (pin "2") (pinfunction "B_2") (pintype "passive"))
      (node (ref "R155") (pin "1") (pinfunction "1_1") (pintype "passive"))
    )
    (net (code "190") (name "Net-(Q14-C)") (class "Default")
      (node (ref "Q14") (pin "3") (pinfunction "C_3") (pintype "passive"))
      (node (ref "Q15") (pin "2") (pinfunction "B_2") (pintype "passive"))
      (node (ref "R157") (pin "2") (pinfunction "2_2") (pintype "passive"))
    )
    (net (code "191") (name "Net-(Q14-E)") (class "Default")
      (node (ref "Q14") (pin "1") (pinfunction "E_1") (pintype "passive"))
      (node (ref "Q15") (pin "1") (pinfunction "E_1") (pintype "passive"))
      (node (ref "R156") (pin "1") (pinfunction "1_1") (pintype "passive"))
    )
    (net (code "192") (name "Net-(Q15-C)") (class "Default")
      (node (ref "C19") (pin "2") (pinfunction "2_2") (pintype "passive"))
      (node (ref "Q15") (pin "3") (pinfunction "C_3") (pintype "passive"))
      (node (ref "R158") (pin "2") (pinfunction "2_2") (pintype "passive"))
    )
    (net (code "193") (name "Net-(Q16-B)") (class "Default")
      (node (ref "Q16") (pin "2") (pinfunction "B_2") (pintype "passive"))
      (node (ref "Q19") (pin "3") (pinfunction "C_3") (pintype "passive"))
      (node (ref "R167") (pin "1") (pinfunction "1_1") (pintype "passive"))
    )
    (net (code "194") (name "Net-(Q16-C)") (class "Default")
      (node (ref "I28") (pin "A") (pinfunction "A_A") (pintype "passive"))
      (node (ref "Q16") (pin "3") (pinfunction "C_3") (pintype "passive"))
      (node (ref "R168") (pin "1") (pinfunction "1_1") (pintype "passive"))
    )
    (net (code "195") (name "Net-(Q16-E)") (class "Default")
      (node (ref "D122") (pin "C") (pinfunction "C_C") (pintype "passive"))
      (node (ref "Q16") (pin "1") (pinfunction "E_1") (pintype "passive"))
      (node (ref "R168") (pin "2") (pinfunction "2_2") (pintype "passive"))
    )
    (net (code "196") (name "Net-(Q17-B)") (class "Default")
      (node (ref "Q17") (pin "2") (pinfunction "B_2") (pintype "passive"))
      (node (ref "R172") (pin "2") (pinfunction "2_2") (pintype "passive"))
    )
    (net (code "197") (name "Net-(Q17-C)") (class "Default")
      (node (ref "Q17") (pin "3") (pinfunction "C_3") (pintype "passive"))
      (node (ref "R163") (pin "1") (pinfunction "1_1") (pintype "passive"))
    )
    (net (code "198") (name "Net-(Q18-B)") (class "Default")
      (node (ref "Q18") (pin "2") (pinfunction "B_2") (pintype "passive"))
      (node (ref "R174") (pin "2") (pinfunction "2_2") (pintype "passive"))
    )
    (net (code "199") (name "Net-(Q18-C)") (class "Default")
      (node (ref "Q18") (pin "3") (pinfunction "C_3") (pintype "passive"))
      (node (ref "R165") (pin "1") (pinfunction "1_1") (pintype "passive"))
    )
    (net (code "200") (name "Net-(Q19-B)") (class "Default")
      (node (ref "Q19") (pin "2") (pinfunction "B_2") (pintype "passive"))
      (node (ref "R166") (pin "2") (pinfunction "2_2") (pintype "passive"))
    )
    (net (code "201") (name "Net-(R10-Pad2)") (class "Default")
      (node (ref "R10") (pin "2") (pinfunction "2_2") (pintype "passive"))
      (node (ref "R11") (pin "2") (pinfunction "2_2") (pintype "passive"))
      (node (ref "R12") (pin "2") (pinfunction "2_2") (pintype "passive"))
      (node (ref "R13") (pin "2") (pinfunction "2_2") (pintype "passive"))
      (node (ref "R14") (pin "2") (pinfunction "2_2") (pintype "passive"))
      (node (ref "R15") (pin "2") (pinfunction "2_2") (pintype "passive"))
      (node (ref "R16") (pin "2") (pinfunction "2_2") (pintype "passive"))
      (node (ref "R17") (pin "2") (pinfunction "2_2") (pintype "passive"))
      (node (ref "R18") (pin "2") (pinfunction "2_2") (pintype "passive"))
      (node (ref "R19") (pin "2") (pinfunction "2_2") (pintype "passive"))
      (node (ref "R20") (pin "2") (pinfunction "2_2") (pintype "passive"))
      (node (ref "R21") (pin "2") (pinfunction "2_2") (pintype "passive"))
      (node (ref "R7") (pin "2") (pinfunction "2_2") (pintype "passive"))
      (node (ref "R8") (pin "2") (pinfunction "2_2") (pintype "passive"))
      (node (ref "R9") (pin "2") (pinfunction "2_2") (pintype "passive"))
    )
    (net (code "202") (name "Net-(R41-Pad1)") (class "Default")
      (node (ref "R41") (pin "1") (pinfunction "1_1") (pintype "passive"))
      (node (ref "R42") (pin "1") (pinfunction "1_1") (pintype "passive"))
    )
    (net (code "203") (name "Net-(R153-Pad2)") (class "Default")
      (node (ref "R153") (pin "2") (pinfunction "2_2") (pintype "passive"))
      (node (ref "R154") (pin "1") (pinfunction "1_1") (pintype "passive"))
    )
    (net (code "204") (name "Net-(R162-Pad1)") (class "Default")
      (node (ref "R162") (pin "1") (pinfunction "1_1") (pintype "passive"))
      (node (ref "R172") (pin "1") (pinfunction "1_1") (pintype "passive"))
    )
    (net (code "205") (name "Net-(R164-Pad1)") (class "Default")
      (node (ref "R164") (pin "1") (pinfunction "1_1") (pintype "passive"))
      (node (ref "R174") (pin "1") (pinfunction "1_1") (pintype "passive"))
    )
    (net (code "206") (name "Net-(S11-A1)") (class "Default")
      (node (ref "R103") (pin "1") (pinfunction "1_1") (pintype "passive"))
      (node (ref "R104") (pin "1") (pinfunction "1_1") (pintype "passive"))
      (node (ref "S11") (pin "L1") (pinfunction "A1_L1") (pintype "bidirectional"))
      (node (ref "S11") (pin "R1") (pinfunction "B1_R1") (pintype "bidirectional"))
    )
    (net (code "207") (name "Net-(S12-A1)") (class "Default")
      (node (ref "R105") (pin "1") (pinfunction "1_1") (pintype "passive"))
      (node (ref "R106") (pin "1") (pinfunction "1_1") (pintype "passive"))
      (node (ref "S12") (pin "L1") (pinfunction "A1_L1") (pintype "bidirectional"))
      (node (ref "S12") (pin "R1") (pinfunction "B1_R1") (pintype "bidirectional"))
    )
    (net (code "208") (name "Net-(S13-A1)") (class "Default")
      (node (ref "R107") (pin "1") (pinfunction "1_1") (pintype "passive"))
      (node (ref "R108") (pin "1") (pinfunction "1_1") (pintype "passive"))
      (node (ref "S13") (pin "L1") (pinfunction "A1_L1") (pintype "bidirectional"))
      (node (ref "S13") (pin "R1") (pinfunction "B1_R1") (pintype "bidirectional"))
    )
    (net (code "209") (name "Net-(S14-A1)") (class "Default")
      (node (ref "R109") (pin "1") (pinfunction "1_1") (pintype "passive"))
      (node (ref "R110") (pin "1") (pinfunction "1_1") (pintype "passive"))
      (node (ref "S14") (pin "L1") (pinfunction "A1_L1") (pintype "bidirectional"))
      (node (ref "S14") (pin "R1") (pinfunction "B1_R1") (pintype "bidirectional"))
    )
    (net (code "210") (name "Net-(S15-A1)") (class "Default")
      (node (ref "R111") (pin "1") (pinfunction "1_1") (pintype "passive"))
      (node (ref "R112") (pin "1") (pinfunction "1_1") (pintype "passive"))
      (node (ref "S15") (pin "L1") (pinfunction "A1_L1") (pintype "bidirectional"))
      (node (ref "S15") (pin "R1") (pinfunction "B1_R1") (pintype "bidirectional"))
    )
    (net (code "211") (name "Net-(S16-A1)") (class "Default")
      (node (ref "R113") (pin "1") (pinfunction "1_1") (pintype "passive"))
      (node (ref "R114") (pin "1") (pinfunction "1_1") (pintype "passive"))
      (node (ref "S16") (pin "L1") (pinfunction "A1_L1") (pintype "bidirectional"))
      (node (ref "S16") (pin "R1") (pinfunction "B1_R1") (pintype "bidirectional"))
    )
    (net (code "212") (name "Net-(S17-A1)") (class "Default")
      (node (ref "R115") (pin "1") (pinfunction "1_1") (pintype "passive"))
      (node (ref "R116") (pin "1") (pinfunction "1_1") (pintype "passive"))
      (node (ref "S17") (pin "L1") (pinfunction "A1_L1") (pintype "bidirectional"))
      (node (ref "S17") (pin "R1") (pinfunction "B1_R1") (pintype "bidirectional"))
    )
    (net (code "213") (name "Net-(S18-A1)") (class "Default")
      (node (ref "R117") (pin "1") (pinfunction "1_1") (pintype "passive"))
      (node (ref "R118") (pin "1") (pinfunction "1_1") (pintype "passive"))
      (node (ref "S18") (pin "L1") (pinfunction "A1_L1") (pintype "bidirectional"))
      (node (ref "S18") (pin "R1") (pinfunction "B1_R1") (pintype "bidirectional"))
    )
    (net (code "214") (name "Net-(S19-A1)") (class "Default")
      (node (ref "R119") (pin "1") (pinfunction "1_1") (pintype "passive"))
      (node (ref "R120") (pin "1") (pinfunction "1_1") (pintype "passive"))
      (node (ref "S19") (pin "L1") (pinfunction "A1_L1") (pintype "bidirectional"))
      (node (ref "S19") (pin "R1") (pinfunction "B1_R1") (pintype "bidirectional"))
    )
    (net (code "215") (name "Net-(S20-A1)") (class "Default")
      (node (ref "R121") (pin "1") (pinfunction "1_1") (pintype "passive"))
      (node (ref "R122") (pin "1") (pinfunction "1_1") (pintype "passive"))
      (node (ref "S20") (pin "L1") (pinfunction "A1_L1") (pintype "bidirectional"))
      (node (ref "S20") (pin "R1") (pinfunction "B1_R1") (pintype "bidirectional"))
    )
    (net (code "216") (name "Net-(S21-A1)") (class "Default")
      (node (ref "R123") (pin "1") (pinfunction "1_1") (pintype "passive"))
      (node (ref "R124") (pin "1") (pinfunction "1_1") (pintype "passive"))
      (node (ref "S21") (pin "L1") (pinfunction "A1_L1") (pintype "bidirectional"))
      (node (ref "S21") (pin "R1") (pinfunction "B1_R1") (pintype "bidirectional"))
    )
    (net (code "217") (name "Net-(S22-A1)") (class "Default")
      (node (ref "R125") (pin "1") (pinfunction "1_1") (pintype "passive"))
      (node (ref "R126") (pin "1") (pinfunction "1_1") (pintype "passive"))
      (node (ref "S22") (pin "L1") (pinfunction "A1_L1") (pintype "bidirectional"))
      (node (ref "S22") (pin "R1") (pinfunction "B1_R1") (pintype "bidirectional"))
    )
    (net (code "218") (name "Net-(SSTP-A1)") (class "Default")
      (node (ref "R48") (pin "1") (pinfunction "1_1") (pintype "passive"))
      (node (ref "R56") (pin "1") (pinfunction "1_1") (pintype "passive"))
      (node (ref "SSTP") (pin "L1") (pinfunction "A1_L1") (pintype "bidirectional"))
      (node (ref "SSTP") (pin "R1") (pinfunction "B1_R1") (pintype "bidirectional"))
    )
    (net (code "219") (name "Net-(SW-A1)") (class "Default")
      (node (ref "R45") (pin "1") (pinfunction "1_1") (pintype "passive"))
      (node (ref "R46") (pin "1") (pinfunction "1_1") (pintype "passive"))
      (node (ref "SW") (pin "L1") (pinfunction "A1_L1") (pintype "bidirectional"))
      (node (ref "SW") (pin "R1") (pinfunction "B1_R1") (pintype "bidirectional"))
    )
    (net (code "220") (name "PAN_LOCK") (class "Default")
      (node (ref "BLUE") (pin "1") (pinfunction "1_1") (pintype "passive"))
      (node (ref "HALT") (pin "L2") (pinfunction "A2_L2") (pintype "bidirectional"))
      (node (ref "HALT") (pin "R2") (pinfunction "B2_R2") (pintype "bidirectional"))
      (node (ref "SSTP") (pin "L2") (pinfunction "A2_L2") (pintype "bidirectional"))
      (node (ref "SSTP") (pin "R2") (pinfunction "B2_R2") (pintype "bidirectional"))
      (node (ref "SW") (pin "L2") (pinfunction "A2_L2") (pintype "bidirectional"))
      (node (ref "SW") (pin "R2") (pinfunction "B2_R2") (pintype "bidirectional"))
    )
    (net (code "221") (name "PULSE_LA") (class "Default")
      (node (ref "Q17") (pin "1") (pinfunction "E_1") (pintype "passive"))
      (node (ref "U$2") (pin "DR2") (pinfunction "1_DR2") (pintype "bidirectional"))
    )
    (net (code "223") (name "SSTP") (class "Default")
      (node (ref "D3") (pin "C") (pinfunction "C_C") (pintype "passive"))
      (node (ref "E13") (pin "1") (pinfunction "I0_1") (pintype "input"))
      (node (ref "R48") (pin "2") (pinfunction "2_2") (pintype "passive"))
    )
    (net (code "224") (name "STATE_EN") (class "Default")
      (node (ref "R143") (pin "1") (pinfunction "1_1") (pintype "passive"))
      (node (ref "S1") (pin "6") (pinfunction "6_6") (pintype "passive"))
    )
    (net (code "225") (name "STATUS_EN") (class "Default")
      (node (ref "R148") (pin "1") (pinfunction "1_1") (pintype "passive"))
      (node (ref "S1") (pin "5") (pinfunction "5_5") (pintype "passive"))
    )
    (net (code "226") (name "SWITCH") (class "Default")
      (node (ref "D1") (pin "C") (pinfunction "C_C") (pintype "passive"))
      (node (ref "R45") (pin "2") (pinfunction "2_2") (pintype "passive"))
      (node (ref "R46") (pin "2") (pinfunction "2_2") (pintype "passive"))
      (node (ref "U$2") (pin "DV2") (pinfunction "1_DV2") (pintype "bidirectional"))
    )
    (net (code "227") (name "TP4") (class "Default")
      (node (ref "U$2") (pin "CJ2") (pinfunction "1_CJ2") (pintype "bidirectional"))
    )
    (net (code "228") (name "TS1") (class "Default")
      (node (ref "U$2") (pin "CK2") (pinfunction "1_CK2") (pintype "bidirectional"))
    )
    (net (code "229") (name "TS3") (class "Default")
      (node (ref "U$2") (pin "CM2") (pinfunction "1_CM2") (pintype "bidirectional"))
    )
    (net (code "230") (name "TS4") (class "Default")
      (node (ref "U$2") (pin "CP2") (pinfunction "1_CP2") (pintype "bidirectional"))
    )
    (net (code "231") (name "U_MODE") (class "Default")
      (node (ref "U$2") (pin "DM2") (pinfunction "1_DM2") (pintype "bidirectional"))
    )
    (net (code "232") (name "VCC") (class "Default")
      (node (ref "C1") (pin "+") (pinfunction "+_+") (pintype "passive"))
      (node (ref "C10") (pin "1") (pinfunction "1_1") (pintype "passive"))
      (node (ref "C11") (pin "1") (pinfunction "1_1") (pintype "passive"))
      (node (ref "C12") (pin "1") (pinfunction "1_1") (pintype "passive"))
      (node (ref "C13") (pin "1") (pinfunction "1_1") (pintype "passive"))
      (node (ref "C14") (pin "1") (pinfunction "1_1") (pintype "passive"))
      (node (ref "C15") (pin "1") (pinfunction "1_1") (pintype "passive"))
      (node (ref "C16") (pin "1") (pinfunction "1_1") (pintype "passive"))
      (node (ref "C2") (pin "+") (pinfunction "+_+") (pintype "passive"))
      (node (ref "C21") (pin "1") (pinfunction "1_1") (pintype "passive"))
      (node (ref "C22") (pin "1") (pinfunction "1_1") (pintype "passive"))
      (node (ref "C23") (pin "1") (pinfunction "1_1") (pintype "passive"))
      (node (ref "C24") (pin "1") (pinfunction "1_1") (pintype "passive"))
      (node (ref "C25") (pin "1") (pinfunction "1_1") (pintype "passive"))
      (node (ref "C26") (pin "1") (pinfunction "1_1") (pintype "passive"))
      (node (ref "C27") (pin "1") (pinfunction "1_1") (pintype "passive"))
      (node (ref "C28") (pin "1") (pinfunction "1_1") (pintype "passive"))
      (node (ref "C29") (pin "1") (pinfunction "1_1") (pintype "passive"))
      (node (ref "C3") (pin "+") (pinfunction "+_+") (pintype "passive"))
      (node (ref "C30") (pin "1") (pinfunction "1_1") (pintype "passive"))
      (node (ref "C31") (pin "1") (pinfunction "1_1") (pintype "passive"))
      (node (ref "C32") (pin "1") (pinfunction "1_1") (pintype "passive"))
      (node (ref "C33") (pin "1") (pinfunction "1_1") (pintype "passive"))
      (node (ref "C4") (pin "+") (pinfunction "+_+") (pintype "passive"))
      (node (ref "C5") (pin "1") (pinfunction "1_1") (pintype "passive"))
      (node (ref "C6") (pin "1") (pinfunction "1_1") (pintype "passive"))
      (node (ref "C7") (pin "1") (pinfunction "1_1") (pintype "passive"))
      (node (ref "C8") (pin "1") (pinfunction "1_1") (pintype "passive"))
      (node (ref "C9") (pin "1") (pinfunction "1_1") (pintype "passive"))
      (node (ref "R104") (pin "2") (pinfunction "2_2") (pintype "passive"))
      (node (ref "R106") (pin "2") (pinfunction "2_2") (pintype "passive"))
      (node (ref "R108") (pin "2") (pinfunction "2_2") (pintype "passive"))
      (node (ref "R110") (pin "2") (pinfunction "2_2") (pintype "passive"))
      (node (ref "R112") (pin "2") (pinfunction "2_2") (pintype "passive"))
      (node (ref "R114") (pin "2") (pinfunction "2_2") (pintype "passive"))
      (node (ref "R116") (pin "2") (pinfunction "2_2") (pintype "passive"))
      (node (ref "R118") (pin "2") (pinfunction "2_2") (pintype "passive"))
      (node (ref "R120") (pin "2") (pinfunction "2_2") (pintype "passive"))
      (node (ref "R122") (pin "2") (pinfunction "2_2") (pintype "passive"))
      (node (ref "R124") (pin "2") (pinfunction "2_2") (pintype "passive"))
      (node (ref "R126") (pin "2") (pinfunction "2_2") (pintype "passive"))
      (node (ref "R142") (pin "2") (pinfunction "2_2") (pintype "passive"))
      (node (ref "R143") (pin "2") (pinfunction "2_2") (pintype "passive"))
      (node (ref "R144") (pin "2") (pinfunction "2_2") (pintype "passive"))
      (node (ref "R145") (pin "2") (pinfunction "2_2") (pintype "passive"))
      (node (ref "R146") (pin "2") (pinfunction "2_2") (pintype "passive"))
      (node (ref "R147") (pin "2") (pinfunction "2_2") (pintype "passive"))
      (node (ref "R152") (pin "2") (pinfunction "2_2") (pintype "passive"))
      (node (ref "R155") (pin "2") (pinfunction "2_2") (pintype "passive"))
      (node (ref "R156") (pin "2") (pinfunction "2_2") (pintype "passive"))
      (node (ref "R161") (pin "2") (pinfunction "2_2") (pintype "passive"))
      (node (ref "R162") (pin "2") (pinfunction "2_2") (pintype "passive"))
      (node (ref "R163") (pin "2") (pinfunction "2_2") (pintype "passive"))
      (node (ref "R164") (pin "2") (pinfunction "2_2") (pintype "passive"))
      (node (ref "R165") (pin "2") (pinfunction "2_2") (pintype "passive"))
      (node (ref "R167") (pin "2") (pinfunction "2_2") (pintype "passive"))
      (node (ref "R169") (pin "1") (pinfunction "1_1") (pintype "passive"))
      (node (ref "R170") (pin "2") (pinfunction "2_2") (pintype "passive"))
      (node (ref "R175") (pin "2") (pinfunction "2_2") (pintype "passive"))
      (node (ref "R39") (pin "2") (pinfunction "2_2") (pintype "passive"))
      (node (ref "R55") (pin "2") (pinfunction "2_2") (pintype "passive"))
      (node (ref "R56") (pin "2") (pinfunction "2_2") (pintype "passive"))
      (node (ref "U$2") (pin "AA2") (pinfunction "1_AA2") (pintype "bidirectional"))
      (node (ref "U$2") (pin "BA2") (pinfunction "1_BA2") (pintype "bidirectional"))
      (node (ref "U$2") (pin "CA2") (pinfunction "1_CA2") (pintype "bidirectional"))
    )
    (net (code "233") (name "WILL_START") (class "Default")
      (node (ref "R153") (pin "1") (pinfunction "1_1") (pintype "passive"))
      (node (ref "R175") (pin "1") (pinfunction "1_1") (pintype "passive"))
    )
    (net (code "234") (name "unconnected-(C20-Pad2)") (class "Default")
      (node (ref "C20") (pin "2") (pinfunction "2_2") (pintype "passive"))
    )
    (net (code "235") (name "unconnected-(E1A-Q3-Pad10)") (class "Default")
      (node (ref "E1") (pin "10") (pinfunction "Q3_10") (pintype "output"))
    )
    (net (code "236") (name "unconnected-(E1A-Q4-Pad15)") (class "Default")
      (node (ref "E1") (pin "15") (pinfunction "Q4_15") (pintype "output"))
    )
    (net (code "237") (name "unconnected-(E1A-~{Q3}-Pad11)") (class "Default")
      (node (ref "E1") (pin "11") (pinfunction "~{Q3}_11") (pintype "output"))
    )
    (net (code "238") (name "unconnected-(E1A-~{Q4}-Pad14)") (class "Default")
      (node (ref "E1") (pin "14") (pinfunction "~{Q4}_14") (pintype "output"))
    )
    (net (code "239") (name "unconnected-(E3A-A0-Pad9)") (class "Default")
      (node (ref "E3") (pin "9") (pinfunction "A0_9") (pintype "tri_state"))
    )
    (net (code "240") (name "unconnected-(E3A-A1-Pad7)") (class "Default")
      (node (ref "E3") (pin "7") (pinfunction "A1_7") (pintype "tri_state"))
    )
    (net (code "241") (name "unconnected-(E3A-A2-Pad6)") (class "Default")
      (node (ref "E3") (pin "6") (pinfunction "A2_6") (pintype "tri_state"))
    )
    (net (code "242") (name "unconnected-(E3A-GS-Pad14)") (class "Default")
      (node (ref "E3") (pin "14") (pinfunction "GS_14") (pintype "tri_state"))
    )
    (net (code "243") (name "unconnected-(E4B-D-Pad12)") (class "Default")
      (node (ref "E4") (pin "12") (pinfunction "D_12") (pintype "input"))
    )
    (net (code "244") (name "unconnected-(E4B-PRE-Pad10)") (class "Default")
      (node (ref "E4") (pin "10") (pinfunction "PRE_10") (pintype "input"))
    )
    (net (code "245") (name "unconnected-(E4B-Q-Pad9)") (class "Default")
      (node (ref "E4") (pin "9") (pinfunction "Q_9") (pintype "output"))
    )
    (net (code "246") (name "unconnected-(E4B-~{Q}-Pad8)") (class "Default")
      (node (ref "E4") (pin "8") (pinfunction "~{Q}_8") (pintype "output"))
    )
    (net (code "247") (name "unconnected-(E5A-I0-Pad4)") (class "Default")
      (node (ref "E5") (pin "4") (pinfunction "I0_4") (pintype "input"))
    )
    (net (code "248") (name "unconnected-(E5A-I1-Pad5)") (class "Default")
      (node (ref "E5") (pin "5") (pinfunction "I1_5") (pintype "input"))
    )
    (net (code "249") (name "unconnected-(E5A-O-Pad3)") (class "Default")
      (node (ref "E5") (pin "3") (pinfunction "O_3") (pintype "output"))
    )
    (net (code "250") (name "unconnected-(E6A-I0-Pad1)") (class "Default")
      (node (ref "E6") (pin "1") (pinfunction "I0_1") (pintype "input"))
    )
    (net (code "251") (name "unconnected-(E6A-I1-Pad2)") (class "Default")
      (node (ref "E6") (pin "2") (pinfunction "I1_2") (pintype "input"))
    )
    (net (code "252") (name "unconnected-(E6A-O-Pad12)") (class "Default")
      (node (ref "E6") (pin "12") (pinfunction "O_12") (pintype "output"))
    )
    (net (code "253") (name "unconnected-(E6C-O-Pad8)") (class "Default")
      (node (ref "E6") (pin "8") (pinfunction "O_8") (pintype "output"))
    )
    (net (code "254") (name "unconnected-(E8A-I0-Pad1)") (class "Default")
      (node (ref "E8") (pin "1") (pinfunction "I0_1") (pintype "input"))
    )
    (net (code "255") (name "unconnected-(E8A-I1-Pad2)") (class "Default")
      (node (ref "E8") (pin "2") (pinfunction "I1_2") (pintype "input"))
    )
    (net (code "256") (name "unconnected-(E8A-I2-Pad13)") (class "Default")
      (node (ref "E8") (pin "13") (pinfunction "I2_13") (pintype "input"))
    )
    (net (code "257") (name "unconnected-(E8A-O-Pad12)") (class "Default")
      (node (ref "E8") (pin "12") (pinfunction "O_12") (pintype "output"))
    )
    (net (code "258") (name "unconnected-(E8B-I0-Pad3)") (class "Default")
      (node (ref "E8") (pin "3") (pinfunction "I0_3") (pintype "input"))
    )
    (net (code "259") (name "unconnected-(E8B-I1-Pad4)") (class "Default")
      (node (ref "E8") (pin "4") (pinfunction "I1_4") (pintype "input"))
    )
    (net (code "260") (name "unconnected-(E8B-I2-Pad5)") (class "Default")
      (node (ref "E8") (pin "5") (pinfunction "I2_5") (pintype "input"))
    )
    (net (code "261") (name "unconnected-(E8B-O-Pad6)") (class "Default")
      (node (ref "E8") (pin "6") (pinfunction "O_6") (pintype "output"))
    )
    (net (code "262") (name "unconnected-(E8C-I0-Pad9)") (class "Default")
      (node (ref "E8") (pin "9") (pinfunction "I0_9") (pintype "input"))
    )
    (net (code "263") (name "unconnected-(E8C-I1-Pad10)") (class "Default")
      (node (ref "E8") (pin "10") (pinfunction "I1_10") (pintype "input"))
    )
    (net (code "264") (name "unconnected-(E8C-I2-Pad11)") (class "Default")
      (node (ref "E8") (pin "11") (pinfunction "I2_11") (pintype "input"))
    )
    (net (code "265") (name "unconnected-(E8C-O-Pad8)") (class "Default")
      (node (ref "E8") (pin "8") (pinfunction "O_8") (pintype "output"))
    )
    (net (code "266") (name "unconnected-(E10A-I0-Pad2)") (class "Default")
      (node (ref "E10") (pin "2") (pinfunction "I0_2") (pintype "input"))
    )
    (net (code "267") (name "unconnected-(E10A-I1-Pad3)") (class "Default")
      (node (ref "E10") (pin "3") (pinfunction "I1_3") (pintype "input"))
    )
    (net (code "268") (name "unconnected-(E10A-O-Pad1)") (class "Default")
      (node (ref "E10") (pin "1") (pinfunction "O_1") (pintype "open_collector"))
    )
    (net (code "269") (name "unconnected-(E12B-I-Pad3)") (class "Default")
      (node (ref "E12") (pin "3") (pinfunction "I_3") (pintype "input"))
    )
    (net (code "270") (name "unconnected-(E12D-I-Pad9)") (class "Default")
      (node (ref "E12") (pin "9") (pinfunction "I_9") (pintype "input"))
    )
    (net (code "271") (name "unconnected-(E12D-O-Pad8)") (class "Default")
      (node (ref "E12") (pin "8") (pinfunction "O_8") (pintype "output"))
    )
    (net (code "272") (name "unconnected-(E12E-O-Pad10)") (class "Default")
      (node (ref "E12") (pin "10") (pinfunction "O_10") (pintype "output"))
    )
    (net (code "273") (name "unconnected-(E13B-O-Pad6)") (class "Default")
      (node (ref "E13") (pin "6") (pinfunction "O_6") (pintype "output"))
    )
    (net (code "274") (name "unconnected-(E13C-I0-Pad9)") (class "Default")
      (node (ref "E13") (pin "9") (pinfunction "I0_9") (pintype "input"))
    )
    (net (code "275") (name "unconnected-(E13C-O-Pad8)") (class "Default")
      (node (ref "E13") (pin "8") (pinfunction "O_8") (pintype "output"))
    )
    (net (code "276") (name "unconnected-(E13D-I0-Pad12)") (class "Default")
      (node (ref "E13") (pin "12") (pinfunction "I0_12") (pintype "input"))
    )
    (net (code "277") (name "unconnected-(E15A-I1-Pad13)") (class "Default")
      (node (ref "E15") (pin "13") (pinfunction "I1_13") (pintype "input"))
    )
    (net (code "278") (name "unconnected-(E15A-I2-Pad12)") (class "Default")
      (node (ref "E15") (pin "12") (pinfunction "I2_12") (pintype "input"))
    )
    (net (code "279") (name "unconnected-(E15A-I3-Pad2)") (class "Default")
      (node (ref "E15") (pin "2") (pinfunction "I3_2") (pintype "input"))
    )
    (net (code "280") (name "unconnected-(E15A-I4-Pad1)") (class "Default")
      (node (ref "E15") (pin "1") (pinfunction "I4_1") (pintype "input"))
    )
    (net (code "281") (name "unconnected-(E15A-I5-Pad9)") (class "Default")
      (node (ref "E15") (pin "9") (pinfunction "I5_9") (pintype "input"))
    )
    (net (code "282") (name "unconnected-(E15A-I6-Pad10)") (class "Default")
      (node (ref "E15") (pin "10") (pinfunction "I6_10") (pintype "input"))
    )
    (net (code "283") (name "unconnected-(E15A-I7-Pad11)") (class "Default")
      (node (ref "E15") (pin "11") (pinfunction "I7_11") (pintype "input"))
    )
    (net (code "284") (name "unconnected-(E15A-I8-Pad3)") (class "Default")
      (node (ref "E15") (pin "3") (pinfunction "I8_3") (pintype "input"))
    )
    (net (code "285") (name "unconnected-(E15A-I9-Pad4)") (class "Default")
      (node (ref "E15") (pin "4") (pinfunction "I9_4") (pintype "input"))
    )
    (net (code "286") (name "unconnected-(E15A-I10-Pad5)") (class "Default")
      (node (ref "E15") (pin "5") (pinfunction "I10_5") (pintype "input"))
    )
    (net (code "287") (name "unconnected-(E15A-O-Pad6)") (class "Default")
      (node (ref "E15") (pin "6") (pinfunction "O_6") (pintype "output"))
    )
    (net (code "288") (name "unconnected-(E16A-I1-Pad13)") (class "Default")
      (node (ref "E16") (pin "13") (pinfunction "I1_13") (pintype "input"))
    )
    (net (code "289") (name "unconnected-(E16A-I2-Pad12)") (class "Default")
      (node (ref "E16") (pin "12") (pinfunction "I2_12") (pintype "input"))
    )
    (net (code "290") (name "unconnected-(E16A-I3-Pad2)") (class "Default")
      (node (ref "E16") (pin "2") (pinfunction "I3_2") (pintype "input"))
    )
    (net (code "291") (name "unconnected-(E16A-I4-Pad1)") (class "Default")
      (node (ref "E16") (pin "1") (pinfunction "I4_1") (pintype "input"))
    )
    (net (code "292") (name "unconnected-(E16A-I5-Pad9)") (class "Default")
      (node (ref "E16") (pin "9") (pinfunction "I5_9") (pintype "input"))
    )
    (net (code "293") (name "unconnected-(E16A-I6-Pad10)") (class "Default")
      (node (ref "E16") (pin "10") (pinfunction "I6_10") (pintype "input"))
    )
    (net (code "294") (name "unconnected-(E16A-I7-Pad11)") (class "Default")
      (node (ref "E16") (pin "11") (pinfunction "I7_11") (pintype "input"))
    )
    (net (code "295") (name "unconnected-(E16A-I8-Pad3)") (class "Default")
      (node (ref "E16") (pin "3") (pinfunction "I8_3") (pintype "input"))
    )
    (net (code "296") (name "unconnected-(E16A-I9-Pad4)") (class "Default")
      (node (ref "E16") (pin "4") (pinfunction "I9_4") (pintype "input"))
    )
    (net (code "297") (name "unconnected-(E16A-I10-Pad5)") (class "Default")
      (node (ref "E16") (pin "5") (pinfunction "I10_5") (pintype "input"))
    )
    (net (code "298") (name "unconnected-(E16A-O-Pad6)") (class "Default")
      (node (ref "E16") (pin "6") (pinfunction "O_6") (pintype "output"))
    )
    (net (code "299") (name "unconnected-(E17A-I0-Pad2)") (class "Default")
      (node (ref "E17") (pin "2") (pinfunction "I0_2") (pintype "input"))
    )
    (net (code "300") (name "unconnected-(E17A-I1-Pad3)") (class "Default")
      (node (ref "E17") (pin "3") (pinfunction "I1_3") (pintype "input"))
    )
    (net (code "301") (name "unconnected-(E17A-O-Pad1)") (class "Default")
      (node (ref "E17") (pin "1") (pinfunction "O_1") (pintype "open_collector"))
    )
    (net (code "302") (name "unconnected-(E18A-B-Pad2)") (class "Default")
      (node (ref "E18") (pin "2") (pinfunction "B_2") (pintype "input"))
    )
    (net (code "303") (name "unconnected-(E18A-C-Pad14)") (class "Default")
      (node (ref "E18") (pin "14") (pinfunction "C_14") (pintype "input"))
    )
    (net (code "304") (name "unconnected-(E18A-CLR-Pad3)") (class "Default")
      (node (ref "E18") (pin "3") (pinfunction "CLR_3") (pintype "input"))
    )
    (net (code "305") (name "unconnected-(E18A-Q-Pad13)") (class "Default")
      (node (ref "E18") (pin "13") (pinfunction "Q_13") (pintype "output"))
    )
    (net (code "306") (name "unconnected-(E18A-R{slash}C-Pad15)") (class "Default")
      (node (ref "E18") (pin "15") (pinfunction "R/C_15") (pintype "input"))
    )
    (net (code "307") (name "unconnected-(E18B-C-Pad6)") (class "Default")
      (node (ref "E18") (pin "6") (pinfunction "C_6") (pintype "input"))
    )
    (net (code "308") (name "unconnected-(E18B-CLR-Pad11)") (class "Default")
      (node (ref "E18") (pin "11") (pinfunction "CLR_11") (pintype "input"))
    )
    (net (code "309") (name "unconnected-(E18B-Q-Pad5)") (class "Default")
      (node (ref "E18") (pin "5") (pinfunction "Q_5") (pintype "output"))
    )
    (net (code "310") (name "unconnected-(E18B-R{slash}C-Pad7)") (class "Default")
      (node (ref "E18") (pin "7") (pinfunction "R/C_7") (pintype "input"))
    )
    (net (code "311") (name "unconnected-(E18B-~{Q}-Pad12)") (class "Default")
      (node (ref "E18") (pin "12") (pinfunction "~{Q}_12") (pintype "output"))
    )
    (net (code "312") (name "unconnected-(E19A-I1-Pad13)") (class "Default")
      (node (ref "E19") (pin "13") (pinfunction "I1_13") (pintype "input"))
    )
    (net (code "313") (name "unconnected-(E19A-I2-Pad12)") (class "Default")
      (node (ref "E19") (pin "12") (pinfunction "I2_12") (pintype "input"))
    )
    (net (code "314") (name "unconnected-(E19A-I3-Pad2)") (class "Default")
      (node (ref "E19") (pin "2") (pinfunction "I3_2") (pintype "input"))
    )
    (net (code "315") (name "unconnected-(E19A-I4-Pad1)") (class "Default")
      (node (ref "E19") (pin "1") (pinfunction "I4_1") (pintype "input"))
    )
    (net (code "316") (name "unconnected-(E19A-I5-Pad9)") (class "Default")
      (node (ref "E19") (pin "9") (pinfunction "I5_9") (pintype "input"))
    )
    (net (code "317") (name "unconnected-(E19A-I6-Pad10)") (class "Default")
      (node (ref "E19") (pin "10") (pinfunction "I6_10") (pintype "input"))
    )
    (net (code "318") (name "unconnected-(E19A-I7-Pad11)") (class "Default")
      (node (ref "E19") (pin "11") (pinfunction "I7_11") (pintype "input"))
    )
    (net (code "319") (name "unconnected-(E19A-I8-Pad3)") (class "Default")
      (node (ref "E19") (pin "3") (pinfunction "I8_3") (pintype "input"))
    )
    (net (code "320") (name "unconnected-(E19A-I9-Pad4)") (class "Default")
      (node (ref "E19") (pin "4") (pinfunction "I9_4") (pintype "input"))
    )
    (net (code "321") (name "unconnected-(E19A-I10-Pad5)") (class "Default")
      (node (ref "E19") (pin "5") (pinfunction "I10_5") (pintype "input"))
    )
    (net (code "322") (name "unconnected-(E19A-O-Pad6)") (class "Default")
      (node (ref "E19") (pin "6") (pinfunction "O_6") (pintype "output"))
    )
    (net (code "323") (name "unconnected-(E20A-O-Pad6)") (class "Default")
      (node (ref "E20") (pin "6") (pinfunction "O_6") (pintype "output"))
    )
    (net (code "324") (name "unconnected-(E20B-I2-Pad12)") (class "Default")
      (node (ref "E20") (pin "12") (pinfunction "I2_12") (pintype "input"))
    )
    (net (code "325") (name "unconnected-(E20B-O-Pad8)") (class "Default")
      (node (ref "E20") (pin "8") (pinfunction "O_8") (pintype "output"))
    )
    (net (code "326") (name "unconnected-(E21A-I1-Pad13)") (class "Default")
      (node (ref "E21") (pin "13") (pinfunction "I1_13") (pintype "input"))
    )
    (net (code "327") (name "unconnected-(E21A-I2-Pad12)") (class "Default")
      (node (ref "E21") (pin "12") (pinfunction "I2_12") (pintype "input"))
    )
    (net (code "328") (name "unconnected-(E21A-I3-Pad2)") (class "Default")
      (node (ref "E21") (pin "2") (pinfunction "I3_2") (pintype "input"))
    )
    (net (code "329") (name "unconnected-(E21A-I4-Pad1)") (class "Default")
      (node (ref "E21") (pin "1") (pinfunction "I4_1") (pintype "input"))
    )
    (net (code "330") (name "unconnected-(E21A-I5-Pad9)") (class "Default")
      (node (ref "E21") (pin "9") (pinfunction "I5_9") (pintype "input"))
    )
    (net (code "331") (name "unconnected-(E21A-I6-Pad10)") (class "Default")
      (node (ref "E21") (pin "10") (pinfunction "I6_10") (pintype "input"))
    )
    (net (code "332") (name "unconnected-(E21A-I7-Pad11)") (class "Default")
      (node (ref "E21") (pin "11") (pinfunction "I7_11") (pintype "input"))
    )
    (net (code "333") (name "unconnected-(E21A-I8-Pad3)") (class "Default")
      (node (ref "E21") (pin "3") (pinfunction "I8_3") (pintype "input"))
    )
    (net (code "334") (name "unconnected-(E21A-I9-Pad4)") (class "Default")
      (node (ref "E21") (pin "4") (pinfunction "I9_4") (pintype "input"))
    )
    (net (code "335") (name "unconnected-(E21A-I10-Pad5)") (class "Default")
      (node (ref "E21") (pin "5") (pinfunction "I10_5") (pintype "input"))
    )
    (net (code "336") (name "unconnected-(E21A-O-Pad6)") (class "Default")
      (node (ref "E21") (pin "6") (pinfunction "O_6") (pintype "output"))
    )
    (net (code "337") (name "unconnected-(E22F-I-Pad13)") (class "Default")
      (node (ref "E22") (pin "13") (pinfunction "I_13") (pintype "input"))
    )
    (net (code "338") (name "unconnected-(E22F-O-Pad12)") (class "Default")
      (node (ref "E22") (pin "12") (pinfunction "O_12") (pintype "output"))
    )
    (net (code "339") (name "unconnected-(E23A-I1-Pad13)") (class "Default")
      (node (ref "E23") (pin "13") (pinfunction "I1_13") (pintype "input"))
    )
    (net (code "340") (name "unconnected-(E23A-I2-Pad12)") (class "Default")
      (node (ref "E23") (pin "12") (pinfunction "I2_12") (pintype "input"))
    )
    (net (code "341") (name "unconnected-(E23A-I3-Pad2)") (class "Default")
      (node (ref "E23") (pin "2") (pinfunction "I3_2") (pintype "input"))
    )
    (net (code "342") (name "unconnected-(E23A-I4-Pad1)") (class "Default")
      (node (ref "E23") (pin "1") (pinfunction "I4_1") (pintype "input"))
    )
    (net (code "343") (name "unconnected-(E23A-I5-Pad9)") (class "Default")
      (node (ref "E23") (pin "9") (pinfunction "I5_9") (pintype "input"))
    )
    (net (code "344") (name "unconnected-(E23A-I6-Pad10)") (class "Default")
      (node (ref "E23") (pin "10") (pinfunction "I6_10") (pintype "input"))
    )
    (net (code "345") (name "unconnected-(E23A-I7-Pad11)") (class "Default")
      (node (ref "E23") (pin "11") (pinfunction "I7_11") (pintype "input"))
    )
    (net (code "346") (name "unconnected-(E23A-I8-Pad3)") (class "Default")
      (node (ref "E23") (pin "3") (pinfunction "I8_3") (pintype "input"))
    )
    (net (code "347") (name "unconnected-(E23A-I9-Pad4)") (class "Default")
      (node (ref "E23") (pin "4") (pinfunction "I9_4") (pintype "input"))
    )
    (net (code "348") (name "unconnected-(E23A-I10-Pad5)") (class "Default")
      (node (ref "E23") (pin "5") (pinfunction "I10_5") (pintype "input"))
    )
    (net (code "349") (name "unconnected-(E23A-O-Pad6)") (class "Default")
      (node (ref "E23") (pin "6") (pinfunction "O_6") (pintype "output"))
    )
    (net (code "350") (name "unconnected-(E24A-I1-Pad13)") (class "Default")
      (node (ref "E24") (pin "13") (pinfunction "I1_13") (pintype "input"))
    )
    (net (code "351") (name "unconnected-(E24A-I2-Pad12)") (class "Default")
      (node (ref "E24") (pin "12") (pinfunction "I2_12") (pintype "input"))
    )
    (net (code "352") (name "unconnected-(E24A-I3-Pad2)") (class "Default")
      (node (ref "E24") (pin "2") (pinfunction "I3_2") (pintype "input"))
    )
    (net (code "353") (name "unconnected-(E24A-I4-Pad1)") (class "Default")
      (node (ref "E24") (pin "1") (pinfunction "I4_1") (pintype "input"))
    )
    (net (code "354") (name "unconnected-(E24A-I5-Pad9)") (class "Default")
      (node (ref "E24") (pin "9") (pinfunction "I5_9") (pintype "input"))
    )
    (net (code "355") (name "unconnected-(E24A-I6-Pad10)") (class "Default")
      (node (ref "E24") (pin "10") (pinfunction "I6_10") (pintype "input"))
    )
    (net (code "356") (name "unconnected-(E24A-I7-Pad11)") (class "Default")
      (node (ref "E24") (pin "11") (pinfunction "I7_11") (pintype "input"))
    )
    (net (code "357") (name "unconnected-(E24A-I8-Pad3)") (class "Default")
      (node (ref "E24") (pin "3") (pinfunction "I8_3") (pintype "input"))
    )
    (net (code "358") (name "unconnected-(E24A-I9-Pad4)") (class "Default")
      (node (ref "E24") (pin "4") (pinfunction "I9_4") (pintype "input"))
    )
    (net (code "359") (name "unconnected-(E24A-I10-Pad5)") (class "Default")
      (node (ref "E24") (pin "5") (pinfunction "I10_5") (pintype "input"))
    )
    (net (code "360") (name "unconnected-(E24A-O-Pad6)") (class "Default")
      (node (ref "E24") (pin "6") (pinfunction "O_6") (pintype "output"))
    )
    (net (code "361") (name "unconnected-(E25A-I5-Pad11)") (class "Default")
      (node (ref "E25") (pin "11") (pinfunction "I5_11") (pintype "input"))
    )
    (net (code "362") (name "unconnected-(E25A-I6-Pad12)") (class "Default")
      (node (ref "E25") (pin "12") (pinfunction "I6_12") (pintype "input"))
    )
    (net (code "363") (name "unconnected-(E27A-I0-Pad2)") (class "Default")
      (node (ref "E27") (pin "2") (pinfunction "I0_2") (pintype "input"))
    )
    (net (code "364") (name "unconnected-(E27A-I1-Pad3)") (class "Default")
      (node (ref "E27") (pin "3") (pinfunction "I1_3") (pintype "input"))
    )
    (net (code "365") (name "unconnected-(E27A-O-Pad1)") (class "Default")
      (node (ref "E27") (pin "1") (pinfunction "O_1") (pintype "open_collector"))
    )
    (net (code "366") (name "unconnected-(E28A-I1-Pad13)") (class "Default")
      (node (ref "E28") (pin "13") (pinfunction "I1_13") (pintype "input"))
    )
    (net (code "367") (name "unconnected-(E28A-I2-Pad12)") (class "Default")
      (node (ref "E28") (pin "12") (pinfunction "I2_12") (pintype "input"))
    )
    (net (code "368") (name "unconnected-(E28A-I3-Pad2)") (class "Default")
      (node (ref "E28") (pin "2") (pinfunction "I3_2") (pintype "input"))
    )
    (net (code "369") (name "unconnected-(E28A-I4-Pad1)") (class "Default")
      (node (ref "E28") (pin "1") (pinfunction "I4_1") (pintype "input"))
    )
    (net (code "370") (name "unconnected-(E28A-I5-Pad9)") (class "Default")
      (node (ref "E28") (pin "9") (pinfunction "I5_9") (pintype "input"))
    )
    (net (code "371") (name "unconnected-(E28A-I6-Pad10)") (class "Default")
      (node (ref "E28") (pin "10") (pinfunction "I6_10") (pintype "input"))
    )
    (net (code "372") (name "unconnected-(E28A-I7-Pad11)") (class "Default")
      (node (ref "E28") (pin "11") (pinfunction "I7_11") (pintype "input"))
    )
    (net (code "373") (name "unconnected-(E28A-I8-Pad3)") (class "Default")
      (node (ref "E28") (pin "3") (pinfunction "I8_3") (pintype "input"))
    )
    (net (code "374") (name "unconnected-(E28A-I9-Pad4)") (class "Default")
      (node (ref "E28") (pin "4") (pinfunction "I9_4") (pintype "input"))
    )
    (net (code "375") (name "unconnected-(E28A-I10-Pad5)") (class "Default")
      (node (ref "E28") (pin "5") (pinfunction "I10_5") (pintype "input"))
    )
    (net (code "376") (name "unconnected-(E28A-O-Pad6)") (class "Default")
      (node (ref "E28") (pin "6") (pinfunction "O_6") (pintype "output"))
    )
    (net (code "377") (name "unconnected-(E30A-I1-Pad13)") (class "Default")
      (node (ref "E30") (pin "13") (pinfunction "I1_13") (pintype "input"))
    )
    (net (code "378") (name "unconnected-(E30A-I2-Pad12)") (class "Default")
      (node (ref "E30") (pin "12") (pinfunction "I2_12") (pintype "input"))
    )
    (net (code "379") (name "unconnected-(E30A-I3-Pad2)") (class "Default")
      (node (ref "E30") (pin "2") (pinfunction "I3_2") (pintype "input"))
    )
    (net (code "380") (name "unconnected-(E30A-I4-Pad1)") (class "Default")
      (node (ref "E30") (pin "1") (pinfunction "I4_1") (pintype "input"))
    )
    (net (code "381") (name "unconnected-(E30A-I5-Pad9)") (class "Default")
      (node (ref "E30") (pin "9") (pinfunction "I5_9") (pintype "input"))
    )
    (net (code "382") (name "unconnected-(E30A-I6-Pad10)") (class "Default")
      (node (ref "E30") (pin "10") (pinfunction "I6_10") (pintype "input"))
    )
    (net (code "383") (name "unconnected-(E30A-I7-Pad11)") (class "Default")
      (node (ref "E30") (pin "11") (pinfunction "I7_11") (pintype "input"))
    )
    (net (code "384") (name "unconnected-(E30A-I8-Pad3)") (class "Default")
      (node (ref "E30") (pin "3") (pinfunction "I8_3") (pintype "input"))
    )
    (net (code "385") (name "unconnected-(E30A-I9-Pad4)") (class "Default")
      (node (ref "E30") (pin "4") (pinfunction "I9_4") (pintype "input"))
    )
    (net (code "386") (name "unconnected-(E30A-I10-Pad5)") (class "Default")
      (node (ref "E30") (pin "5") (pinfunction "I10_5") (pintype "input"))
    )
    (net (code "387") (name "unconnected-(E30A-O-Pad6)") (class "Default")
      (node (ref "E30") (pin "6") (pinfunction "O_6") (pintype "output"))
    )
    (net (code "388") (name "unconnected-(E31F-I-Pad13)") (class "Default")
      (node (ref "E31") (pin "13") (pinfunction "I_13") (pintype "input"))
    )
    (net (code "389") (name "unconnected-(E31F-O-Pad12)") (class "Default")
      (node (ref "E31") (pin "12") (pinfunction "O_12") (pintype "output"))
    )
    (net (code "390") (name "unconnected-(E32A-I1-Pad13)") (class "Default")
      (node (ref "E32") (pin "13") (pinfunction "I1_13") (pintype "input"))
    )
    (net (code "391") (name "unconnected-(E32A-I2-Pad12)") (class "Default")
      (node (ref "E32") (pin "12") (pinfunction "I2_12") (pintype "input"))
    )
    (net (code "392") (name "unconnected-(E32A-I3-Pad2)") (class "Default")
      (node (ref "E32") (pin "2") (pinfunction "I3_2") (pintype "input"))
    )
    (net (code "393") (name "unconnected-(E32A-I4-Pad1)") (class "Default")
      (node (ref "E32") (pin "1") (pinfunction "I4_1") (pintype "input"))
    )
    (net (code "394") (name "unconnected-(E32A-I5-Pad9)") (class "Default")
      (node (ref "E32") (pin "9") (pinfunction "I5_9") (pintype "input"))
    )
    (net (code "395") (name "unconnected-(E32A-I6-Pad10)") (class "Default")
      (node (ref "E32") (pin "10") (pinfunction "I6_10") (pintype "input"))
    )
    (net (code "396") (name "unconnected-(E32A-I7-Pad11)") (class "Default")
      (node (ref "E32") (pin "11") (pinfunction "I7_11") (pintype "input"))
    )
    (net (code "397") (name "unconnected-(E32A-I8-Pad3)") (class "Default")
      (node (ref "E32") (pin "3") (pinfunction "I8_3") (pintype "input"))
    )
    (net (code "398") (name "unconnected-(E32A-I9-Pad4)") (class "Default")
      (node (ref "E32") (pin "4") (pinfunction "I9_4") (pintype "input"))
    )
    (net (code "399") (name "unconnected-(E32A-I10-Pad5)") (class "Default")
      (node (ref "E32") (pin "5") (pinfunction "I10_5") (pintype "input"))
    )
    (net (code "400") (name "unconnected-(E32A-O-Pad6)") (class "Default")
      (node (ref "E32") (pin "6") (pinfunction "O_6") (pintype "output"))
    )
    (net (code "401") (name "unconnected-(E33A-I1-Pad13)") (class "Default")
      (node (ref "E33") (pin "13") (pinfunction "I1_13") (pintype "input"))
    )
    (net (code "402") (name "unconnected-(E33A-I2-Pad12)") (class "Default")
      (node (ref "E33") (pin "12") (pinfunction "I2_12") (pintype "input"))
    )
    (net (code "403") (name "unconnected-(E33A-I3-Pad2)") (class "Default")
      (node (ref "E33") (pin "2") (pinfunction "I3_2") (pintype "input"))
    )
    (net (code "404") (name "unconnected-(E33A-I4-Pad1)") (class "Default")
      (node (ref "E33") (pin "1") (pinfunction "I4_1") (pintype "input"))
    )
    (net (code "405") (name "unconnected-(E33A-I5-Pad9)") (class "Default")
      (node (ref "E33") (pin "9") (pinfunction "I5_9") (pintype "input"))
    )
    (net (code "406") (name "unconnected-(E33A-I6-Pad10)") (class "Default")
      (node (ref "E33") (pin "10") (pinfunction "I6_10") (pintype "input"))
    )
    (net (code "407") (name "unconnected-(E33A-I7-Pad11)") (class "Default")
      (node (ref "E33") (pin "11") (pinfunction "I7_11") (pintype "input"))
    )
    (net (code "408") (name "unconnected-(E33A-I8-Pad3)") (class "Default")
      (node (ref "E33") (pin "3") (pinfunction "I8_3") (pintype "input"))
    )
    (net (code "409") (name "unconnected-(E33A-I9-Pad4)") (class "Default")
      (node (ref "E33") (pin "4") (pinfunction "I9_4") (pintype "input"))
    )
    (net (code "410") (name "unconnected-(E33A-I10-Pad5)") (class "Default")
      (node (ref "E33") (pin "5") (pinfunction "I10_5") (pintype "input"))
    )
    (net (code "411") (name "unconnected-(E33A-O-Pad6)") (class "Default")
      (node (ref "E33") (pin "6") (pinfunction "O_6") (pintype "output"))
    )
    (net (code "412") (name "unconnected-(E34A-I1-Pad13)") (class "Default")
      (node (ref "E34") (pin "13") (pinfunction "I1_13") (pintype "input"))
    )
    (net (code "413") (name "unconnected-(E34A-I2-Pad12)") (class "Default")
      (node (ref "E34") (pin "12") (pinfunction "I2_12") (pintype "input"))
    )
    (net (code "414") (name "unconnected-(E34A-I3-Pad2)") (class "Default")
      (node (ref "E34") (pin "2") (pinfunction "I3_2") (pintype "input"))
    )
    (net (code "415") (name "unconnected-(E34A-I4-Pad1)") (class "Default")
      (node (ref "E34") (pin "1") (pinfunction "I4_1") (pintype "input"))
    )
    (net (code "416") (name "unconnected-(E34A-I5-Pad9)") (class "Default")
      (node (ref "E34") (pin "9") (pinfunction "I5_9") (pintype "input"))
    )
    (net (code "417") (name "unconnected-(E34A-I6-Pad10)") (class "Default")
      (node (ref "E34") (pin "10") (pinfunction "I6_10") (pintype "input"))
    )
    (net (code "418") (name "unconnected-(E34A-I7-Pad11)") (class "Default")
      (node (ref "E34") (pin "11") (pinfunction "I7_11") (pintype "input"))
    )
    (net (code "419") (name "unconnected-(E34A-I8-Pad3)") (class "Default")
      (node (ref "E34") (pin "3") (pinfunction "I8_3") (pintype "input"))
    )
    (net (code "420") (name "unconnected-(E34A-I9-Pad4)") (class "Default")
      (node (ref "E34") (pin "4") (pinfunction "I9_4") (pintype "input"))
    )
    (net (code "421") (name "unconnected-(E34A-I10-Pad5)") (class "Default")
      (node (ref "E34") (pin "5") (pinfunction "I10_5") (pintype "input"))
    )
    (net (code "422") (name "unconnected-(E34A-O-Pad6)") (class "Default")
      (node (ref "E34") (pin "6") (pinfunction "O_6") (pintype "output"))
    )
    (net (code "423") (name "unconnected-(E35A-I0-Pad2)") (class "Default")
      (node (ref "E35") (pin "2") (pinfunction "I0_2") (pintype "input"))
    )
    (net (code "424") (name "unconnected-(E35A-I1-Pad3)") (class "Default")
      (node (ref "E35") (pin "3") (pinfunction "I1_3") (pintype "input"))
    )
    (net (code "425") (name "unconnected-(E35A-O-Pad1)") (class "Default")
      (node (ref "E35") (pin "1") (pinfunction "O_1") (pintype "open_collector"))
    )
    (net (code "426") (name "unconnected-(E36A-I1-Pad13)") (class "Default")
      (node (ref "E36") (pin "13") (pinfunction "I1_13") (pintype "input"))
    )
    (net (code "427") (name "unconnected-(E36A-I2-Pad12)") (class "Default")
      (node (ref "E36") (pin "12") (pinfunction "I2_12") (pintype "input"))
    )
    (net (code "428") (name "unconnected-(E36A-I3-Pad2)") (class "Default")
      (node (ref "E36") (pin "2") (pinfunction "I3_2") (pintype "input"))
    )
    (net (code "429") (name "unconnected-(E36A-I4-Pad1)") (class "Default")
      (node (ref "E36") (pin "1") (pinfunction "I4_1") (pintype "input"))
    )
    (net (code "430") (name "unconnected-(E36A-I5-Pad9)") (class "Default")
      (node (ref "E36") (pin "9") (pinfunction "I5_9") (pintype "input"))
    )
    (net (code "431") (name "unconnected-(E36A-I6-Pad10)") (class "Default")
      (node (ref "E36") (pin "10") (pinfunction "I6_10") (pintype "input"))
    )
    (net (code "432") (name "unconnected-(E36A-I7-Pad11)") (class "Default")
      (node (ref "E36") (pin "11") (pinfunction "I7_11") (pintype "input"))
    )
    (net (code "433") (name "unconnected-(E36A-I8-Pad3)") (class "Default")
      (node (ref "E36") (pin "3") (pinfunction "I8_3") (pintype "input"))
    )
    (net (code "434") (name "unconnected-(E36A-I9-Pad4)") (class "Default")
      (node (ref "E36") (pin "4") (pinfunction "I9_4") (pintype "input"))
    )
    (net (code "435") (name "unconnected-(E36A-I10-Pad5)") (class "Default")
      (node (ref "E36") (pin "5") (pinfunction "I10_5") (pintype "input"))
    )
    (net (code "436") (name "unconnected-(E36A-O-Pad6)") (class "Default")
      (node (ref "E36") (pin "6") (pinfunction "O_6") (pintype "output"))
    )
    (net (code "437") (name "unconnected-(HALT-A3-PadL3)") (class "Default")
      (node (ref "HALT") (pin "L3") (pinfunction "A3_L3") (pintype "bidirectional"))
    )
    (net (code "438") (name "unconnected-(HALT-B3-PadR3)") (class "Default")
      (node (ref "HALT") (pin "R3") (pinfunction "B3_R3") (pintype "bidirectional"))
    )
    (net (code "439") (name "unconnected-(I1-PadA)") (class "Default")
      (node (ref "I1") (pin "A") (pinfunction "A_A") (pintype "passive"))
    )
    (net (code "440") (name "unconnected-(I2-PadA)") (class "Default")
      (node (ref "I2") (pin "A") (pinfunction "A_A") (pintype "passive"))
    )
    (net (code "441") (name "unconnected-(I3-PadA)") (class "Default")
      (node (ref "I3") (pin "A") (pinfunction "A_A") (pintype "passive"))
    )
    (net (code "442") (name "unconnected-(I4-PadA)") (class "Default")
      (node (ref "I4") (pin "A") (pinfunction "A_A") (pintype "passive"))
    )
    (net (code "443") (name "unconnected-(I5-PadA)") (class "Default")
      (node (ref "I5") (pin "A") (pinfunction "A_A") (pintype "passive"))
    )
    (net (code "444") (name "unconnected-(I6-PadA)") (class "Default")
      (node (ref "I6") (pin "A") (pinfunction "A_A") (pintype "passive"))
    )
    (net (code "445") (name "unconnected-(I7-PadA)") (class "Default")
      (node (ref "I7") (pin "A") (pinfunction "A_A") (pintype "passive"))
    )
    (net (code "446") (name "unconnected-(I8-PadA)") (class "Default")
      (node (ref "I8") (pin "A") (pinfunction "A_A") (pintype "passive"))
    )
    (net (code "447") (name "unconnected-(I9-PadA)") (class "Default")
      (node (ref "I9") (pin "A") (pinfunction "A_A") (pintype "passive"))
    )
    (net (code "448") (name "unconnected-(I10-PadA)") (class "Default")
      (node (ref "I10") (pin "A") (pinfunction "A_A") (pintype "passive"))
    )
    (net (code "449") (name "unconnected-(I11-PadA)") (class "Default")
      (node (ref "I11") (pin "A") (pinfunction "A_A") (pintype "passive"))
    )
    (net (code "450") (name "unconnected-(I12-PadA)") (class "Default")
      (node (ref "I12") (pin "A") (pinfunction "A_A") (pintype "passive"))
    )
    (net (code "451") (name "unconnected-(Q7-B-Pad2)") (class "Default")
      (node (ref "Q7") (pin "2") (pinfunction "B_2") (pintype "passive"))
    )
    (net (code "452") (name "unconnected-(Q8-B-Pad2)") (class "Default")
      (node (ref "Q8") (pin "2") (pinfunction "B_2") (pintype "passive"))
    )
    (net (code "453") (name "unconnected-(R27-Pad1)") (class "Default")
      (node (ref "R27") (pin "1") (pinfunction "1_1") (pintype "passive"))
    )
    (net (code "454") (name "unconnected-(R30-Pad1)") (class "Default")
      (node (ref "R30") (pin "1") (pinfunction "1_1") (pintype "passive"))
    )
    (net (code "455") (name "unconnected-(R33-Pad1)") (class "Default")
      (node (ref "R33") (pin "1") (pinfunction "1_1") (pintype "passive"))
    )
    (net (code "456") (name "unconnected-(R36-Pad1)") (class "Default")
      (node (ref "R36") (pin "1") (pinfunction "1_1") (pintype "passive"))
    )
    (net (code "457") (name "unconnected-(R38-Pad1)") (class "Default")
      (node (ref "R38") (pin "1") (pinfunction "1_1") (pintype "passive"))
    )
    (net (code "458") (name "unconnected-(R51-Pad1)") (class "Default")
      (node (ref "R51") (pin "1") (pinfunction "1_1") (pintype "passive"))
    )
    (net (code "459") (name "unconnected-(R54-Pad1)") (class "Default")
      (node (ref "R54") (pin "1") (pinfunction "1_1") (pintype "passive"))
    )
    (net (code "460") (name "unconnected-(R57-Pad1)") (class "Default")
      (node (ref "R57") (pin "1") (pinfunction "1_1") (pintype "passive"))
    )
    (net (code "461") (name "unconnected-(R60-Pad1)") (class "Default")
      (node (ref "R60") (pin "1") (pinfunction "1_1") (pintype "passive"))
    )
    (net (code "462") (name "unconnected-(S11-A3-PadL3)") (class "Default")
      (node (ref "S11") (pin "L3") (pinfunction "A3_L3") (pintype "bidirectional"))
    )
    (net (code "463") (name "unconnected-(S11-B3-PadR3)") (class "Default")
      (node (ref "S11") (pin "R3") (pinfunction "B3_R3") (pintype "bidirectional"))
    )
    (net (code "464") (name "unconnected-(S12-A3-PadL3)") (class "Default")
      (node (ref "S12") (pin "L3") (pinfunction "A3_L3") (pintype "bidirectional"))
    )
    (net (code "465") (name "unconnected-(S12-B3-PadR3)") (class "Default")
      (node (ref "S12") (pin "R3") (pinfunction "B3_R3") (pintype "bidirectional"))
    )
    (net (code "466") (name "unconnected-(S13-A3-PadL3)") (class "Default")
      (node (ref "S13") (pin "L3") (pinfunction "A3_L3") (pintype "bidirectional"))
    )
    (net (code "467") (name "unconnected-(S13-B3-PadR3)") (class "Default")
      (node (ref "S13") (pin "R3") (pinfunction "B3_R3") (pintype "bidirectional"))
    )
    (net (code "468") (name "unconnected-(S14-A3-PadL3)") (class "Default")
      (node (ref "S14") (pin "L3") (pinfunction "A3_L3") (pintype "bidirectional"))
    )
    (net (code "469") (name "unconnected-(S14-B3-PadR3)") (class "Default")
      (node (ref "S14") (pin "R3") (pinfunction "B3_R3") (pintype "bidirectional"))
    )
    (net (code "470") (name "unconnected-(S15-A3-PadL3)") (class "Default")
      (node (ref "S15") (pin "L3") (pinfunction "A3_L3") (pintype "bidirectional"))
    )
    (net (code "471") (name "unconnected-(S15-B3-PadR3)") (class "Default")
      (node (ref "S15") (pin "R3") (pinfunction "B3_R3") (pintype "bidirectional"))
    )
    (net (code "472") (name "unconnected-(S16-A3-PadL3)") (class "Default")
      (node (ref "S16") (pin "L3") (pinfunction "A3_L3") (pintype "bidirectional"))
    )
    (net (code "473") (name "unconnected-(S16-B3-PadR3)") (class "Default")
      (node (ref "S16") (pin "R3") (pinfunction "B3_R3") (pintype "bidirectional"))
    )
    (net (code "474") (name "unconnected-(S17-A3-PadL3)") (class "Default")
      (node (ref "S17") (pin "L3") (pinfunction "A3_L3") (pintype "bidirectional"))
    )
    (net (code "475") (name "unconnected-(S17-B3-PadR3)") (class "Default")
      (node (ref "S17") (pin "R3") (pinfunction "B3_R3") (pintype "bidirectional"))
    )
    (net (code "476") (name "unconnected-(S18-A3-PadL3)") (class "Default")
      (node (ref "S18") (pin "L3") (pinfunction "A3_L3") (pintype "bidirectional"))
    )
    (net (code "477") (name "unconnected-(S18-B3-PadR3)") (class "Default")
      (node (ref "S18") (pin "R3") (pinfunction "B3_R3") (pintype "bidirectional"))
    )
    (net (code "478") (name "unconnected-(S19-A3-PadL3)") (class "Default")
      (node (ref "S19") (pin "L3") (pinfunction "A3_L3") (pintype "bidirectional"))
    )
    (net (code "479") (name "unconnected-(S19-B3-PadR3)") (class "Default")
      (node (ref "S19") (pin "R3") (pinfunction "B3_R3") (pintype "bidirectional"))
    )
    (net (code "480") (name "unconnected-(S20-A3-PadL3)") (class "Default")
      (node (ref "S20") (pin "L3") (pinfunction "A3_L3") (pintype "bidirectional"))
    )
    (net (code "481") (name "unconnected-(S20-B3-PadR3)") (class "Default")
      (node (ref "S20") (pin "R3") (pinfunction "B3_R3") (pintype "bidirectional"))
    )
    (net (code "482") (name "unconnected-(S21-A3-PadL3)") (class "Default")
      (node (ref "S21") (pin "L3") (pinfunction "A3_L3") (pintype "bidirectional"))
    )
    (net (code "483") (name "unconnected-(S21-B3-PadR3)") (class "Default")
      (node (ref "S21") (pin "R3") (pinfunction "B3_R3") (pintype "bidirectional"))
    )
    (net (code "484") (name "unconnected-(S22-A3-PadL3)") (class "Default")
      (node (ref "S22") (pin "L3") (pinfunction "A3_L3") (pintype "bidirectional"))
    )
    (net (code "485") (name "unconnected-(S22-B3-PadR3)") (class "Default")
      (node (ref "S22") (pin "R3") (pinfunction "B3_R3") (pintype "bidirectional"))
    )
    (net (code "486") (name "unconnected-(SSTP-A3-PadL3)") (class "Default")
      (node (ref "SSTP") (pin "L3") (pinfunction "A3_L3") (pintype "bidirectional"))
    )
    (net (code "487") (name "unconnected-(SSTP-B3-PadR3)") (class "Default")
      (node (ref "SSTP") (pin "R3") (pinfunction "B3_R3") (pintype "bidirectional"))
    )
    (net (code "488") (name "unconnected-(SW-A3-PadL3)") (class "Default")
      (node (ref "SW") (pin "L3") (pinfunction "A3_L3") (pintype "bidirectional"))
    )
    (net (code "489") (name "unconnected-(SW-B3-PadR3)") (class "Default")
      (node (ref "SW") (pin "R3") (pinfunction "B3_R3") (pintype "bidirectional"))
    )
    (net (code "490") (name "unconnected-(W1-Pad1)") (class "Default")
      (node (ref "W1") (pin "1") (pinfunction "1_1") (pintype "passive"))
    )
    (net (code "491") (name "unconnected-(W1-Pad2)") (class "Default")
      (node (ref "W1") (pin "2") (pinfunction "2_2") (pintype "passive"))
    )
    (net (code "492") (name "~{CLEAR}") (class "Default")
      (node (ref "E3") (pin "1") (pinfunction "4_1") (pintype "input"))
      (node (ref "E7") (pin "12") (pinfunction "O_12") (pintype "output"))
    )
    (net (code "493") (name "~{CONT}") (class "Default")
      (node (ref "E3") (pin "12") (pinfunction "2_12") (pintype "input"))
      (node (ref "E7") (pin "2") (pinfunction "O_2") (pintype "output"))
    )
    (net (code "494") (name "~{DEP}") (class "Default")
      (node (ref "E3") (pin "10") (pinfunction "0_10") (pintype "input"))
      (node (ref "E7") (pin "6") (pinfunction "O_6") (pintype "output"))
    )
    (net (code "495") (name "~{EXAM}") (class "Default")
      (node (ref "E3") (pin "11") (pinfunction "1_11") (pintype "input"))
      (node (ref "E7") (pin "4") (pinfunction "O_4") (pintype "output"))
    )
    (net (code "496") (name "~{EXTLOAD}") (class "Default")
      (node (ref "E3") (pin "3") (pinfunction "6_3") (pintype "input"))
      (node (ref "E7") (pin "10") (pinfunction "O_10") (pintype "output"))
    )
    (net (code "497") (name "~{FSET}") (class "Default")
      (node (ref "E9") (pin "6") (pinfunction "I0_6") (pintype "input"))
      (node (ref "U$2") (pin "DP2") (pinfunction "1_DP2") (pintype "bidirectional"))
    )
    (net (code "498") (name "~{LOAD}") (class "Default")
      (node (ref "E3") (pin "4") (pinfunction "7_4") (pintype "input"))
      (node (ref "E7") (pin "8") (pinfunction "O_8") (pintype "output"))
    )
    (net (code "499") (name "~{RUN}") (class "Default")
      (node (ref "E12") (pin "1") (pinfunction "I_1") (pintype "input"))
      (node (ref "U$2") (pin "BU2") (pinfunction "1_BU2") (pintype "bidirectional"))
    )
    (net (code "500") (name "~{STOP}") (class "Default")
      (node (ref "E10") (pin "10") (pinfunction "O_10") (pintype "open_collector"))
      (node (ref "U$2") (pin "DS2") (pinfunction "1_DS2") (pintype "bidirectional"))
    )
    (net (code "501") (name "~{T1}") (class "Default")
      (node (ref "E12") (pin "13") (pinfunction "I_13") (pintype "input"))
    )
  )
)
